# mk312.net
KiCad netlist of a schematic drawn in EAGLE
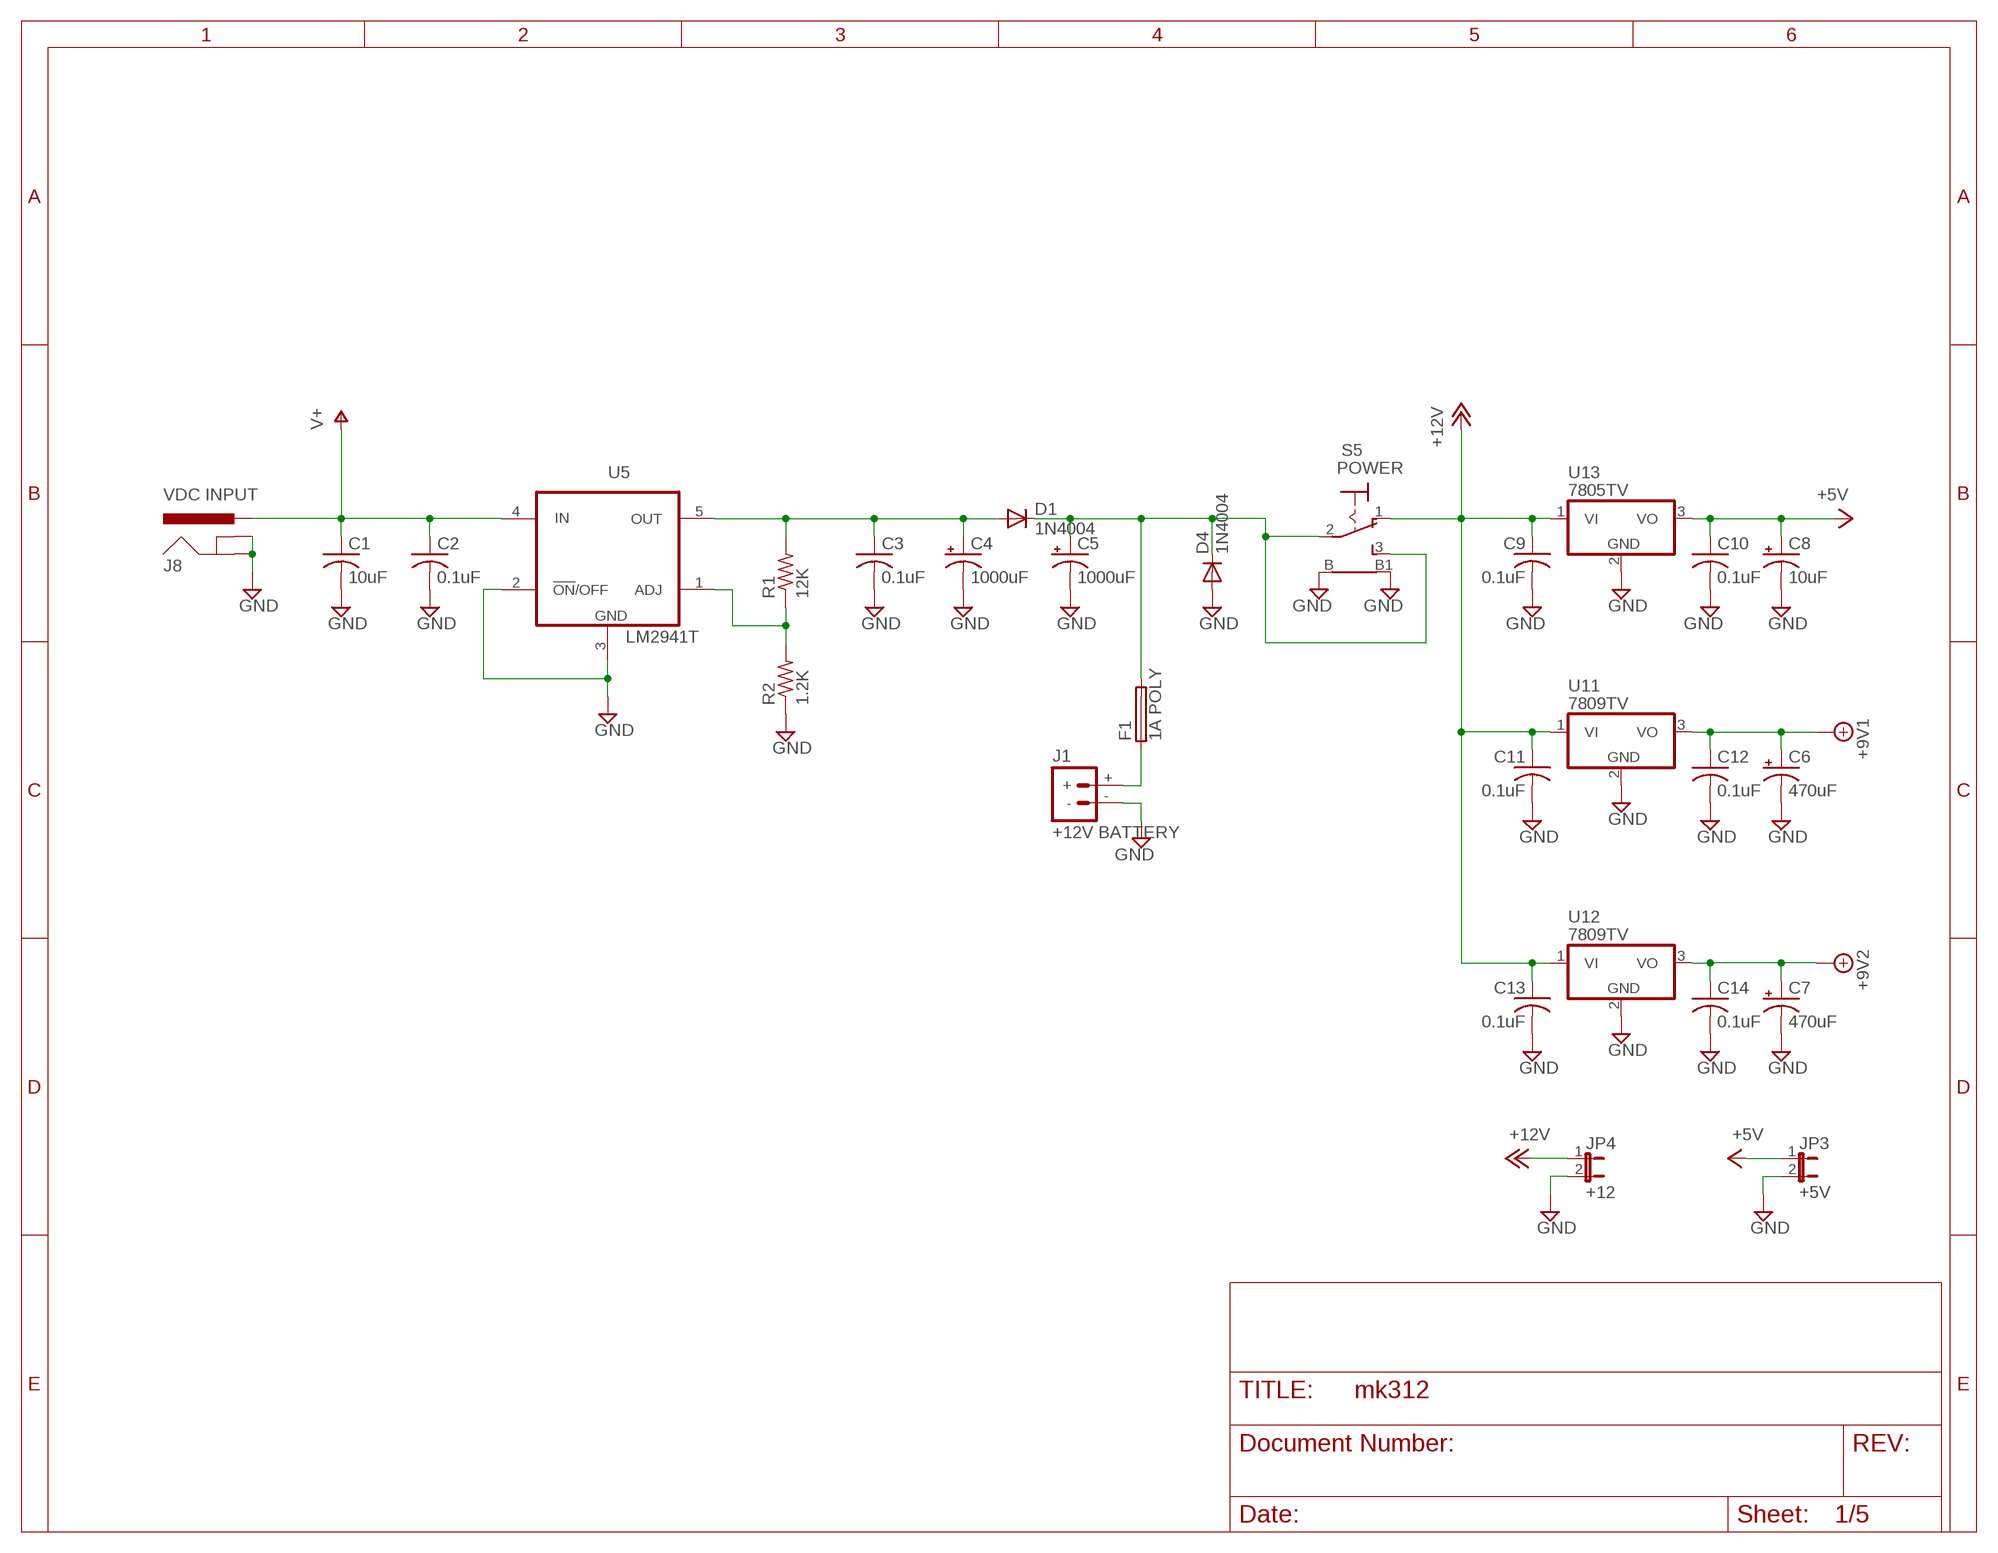
[diagram p0: schematic, sheet 1]
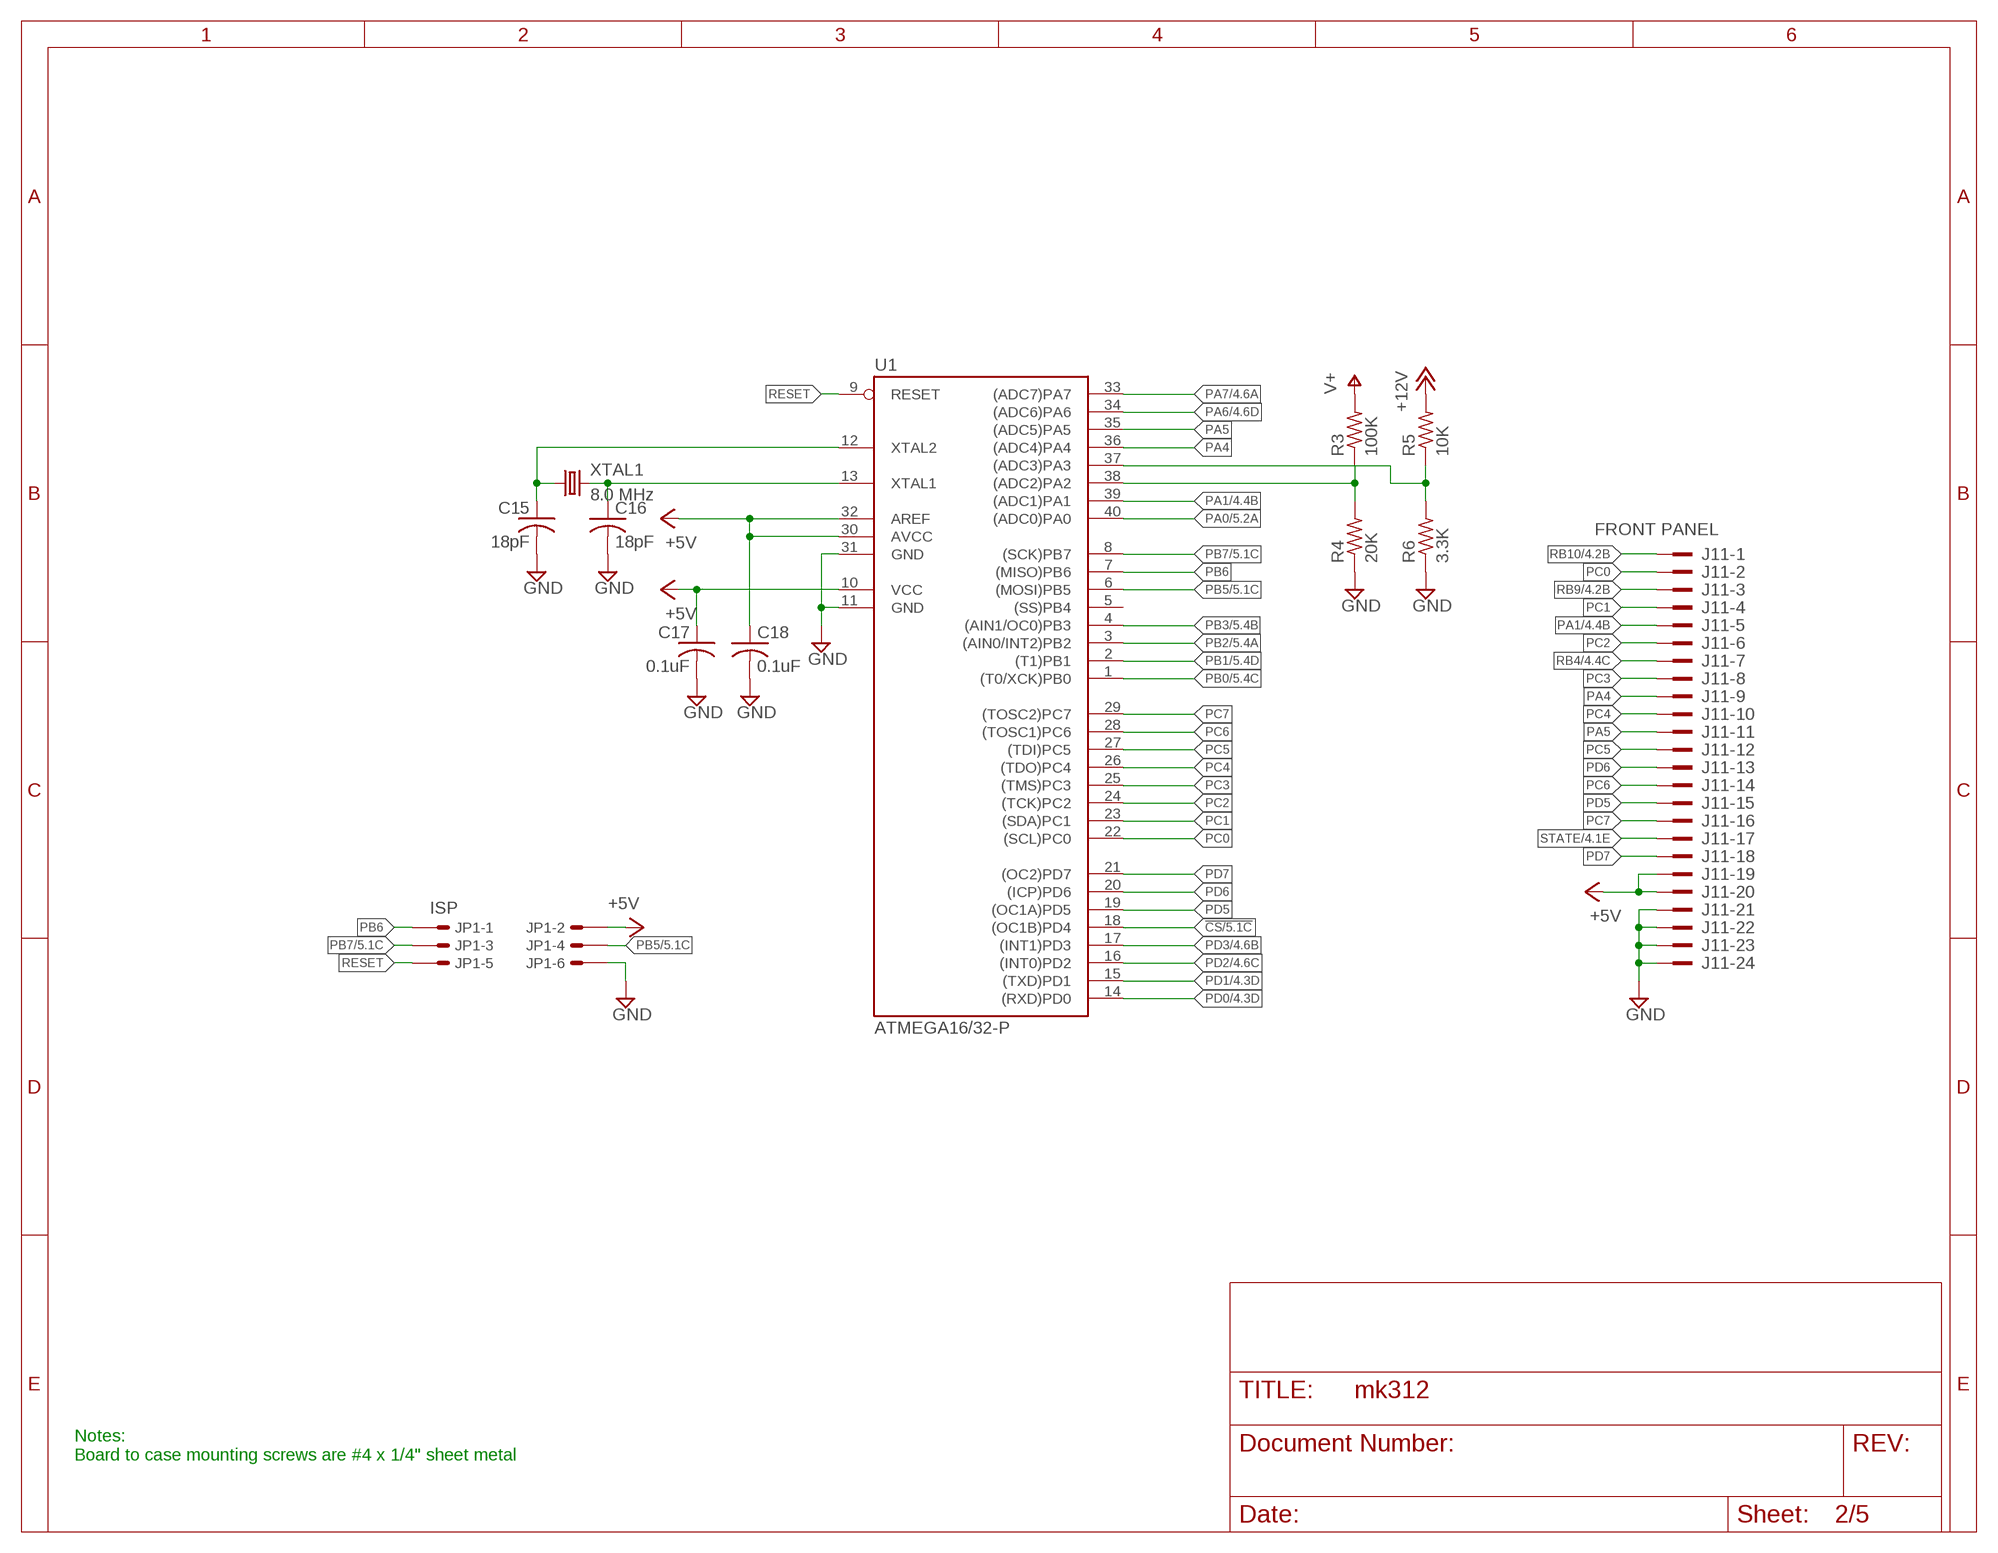
[diagram p1: schematic, sheet 2]
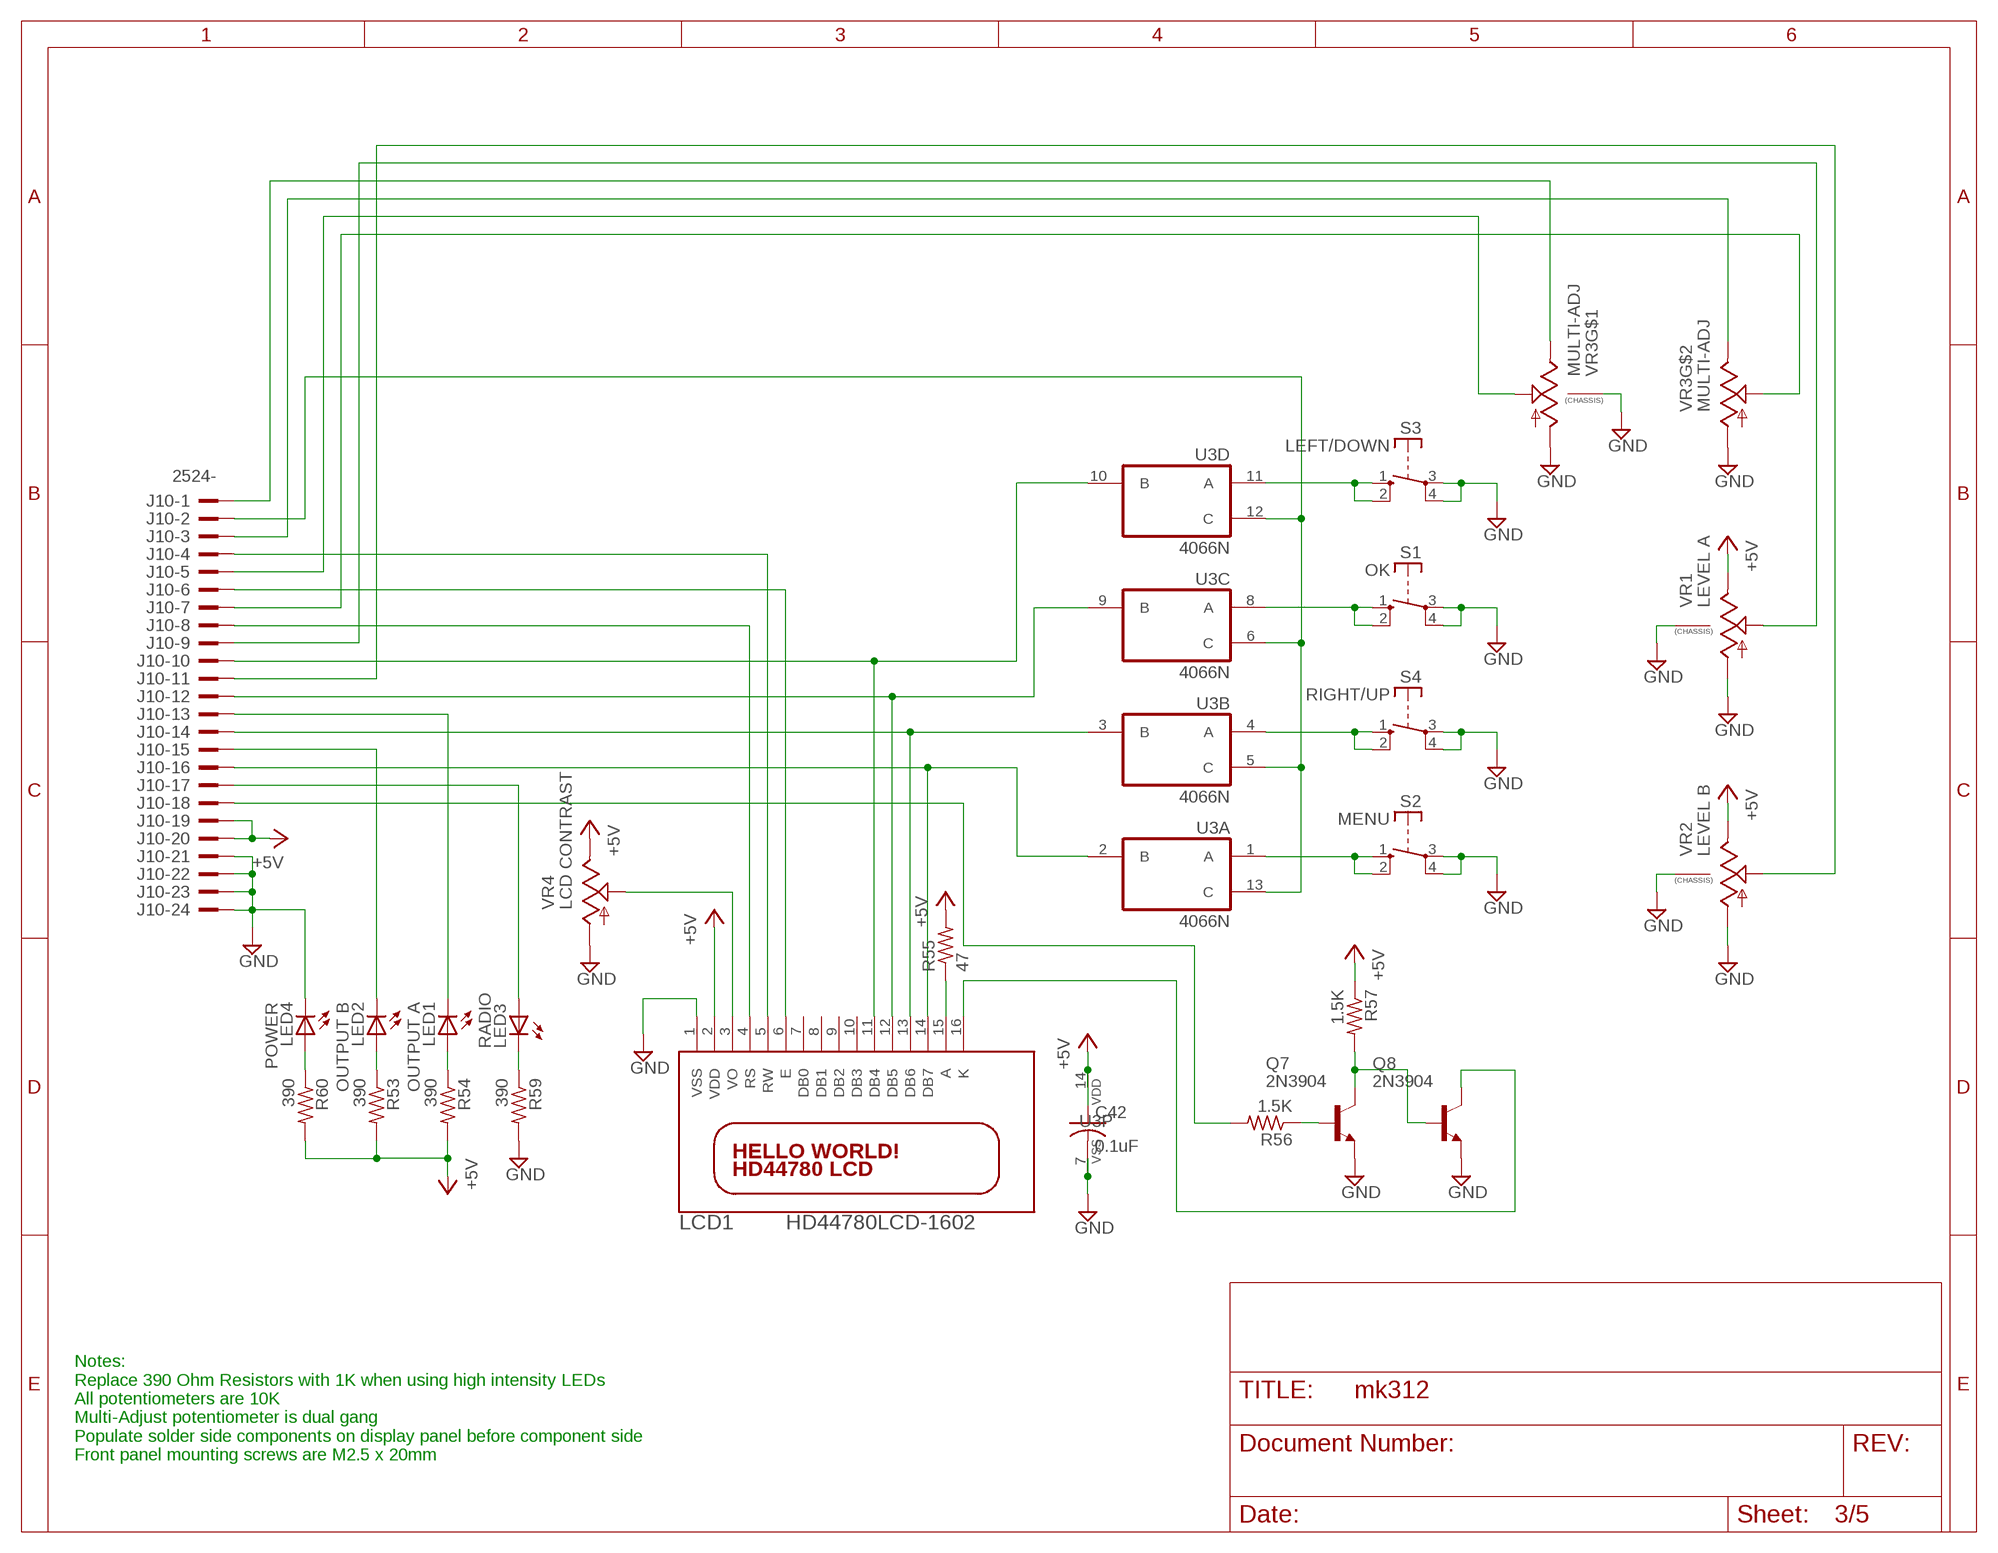
[diagram p2: schematic, sheet 3]
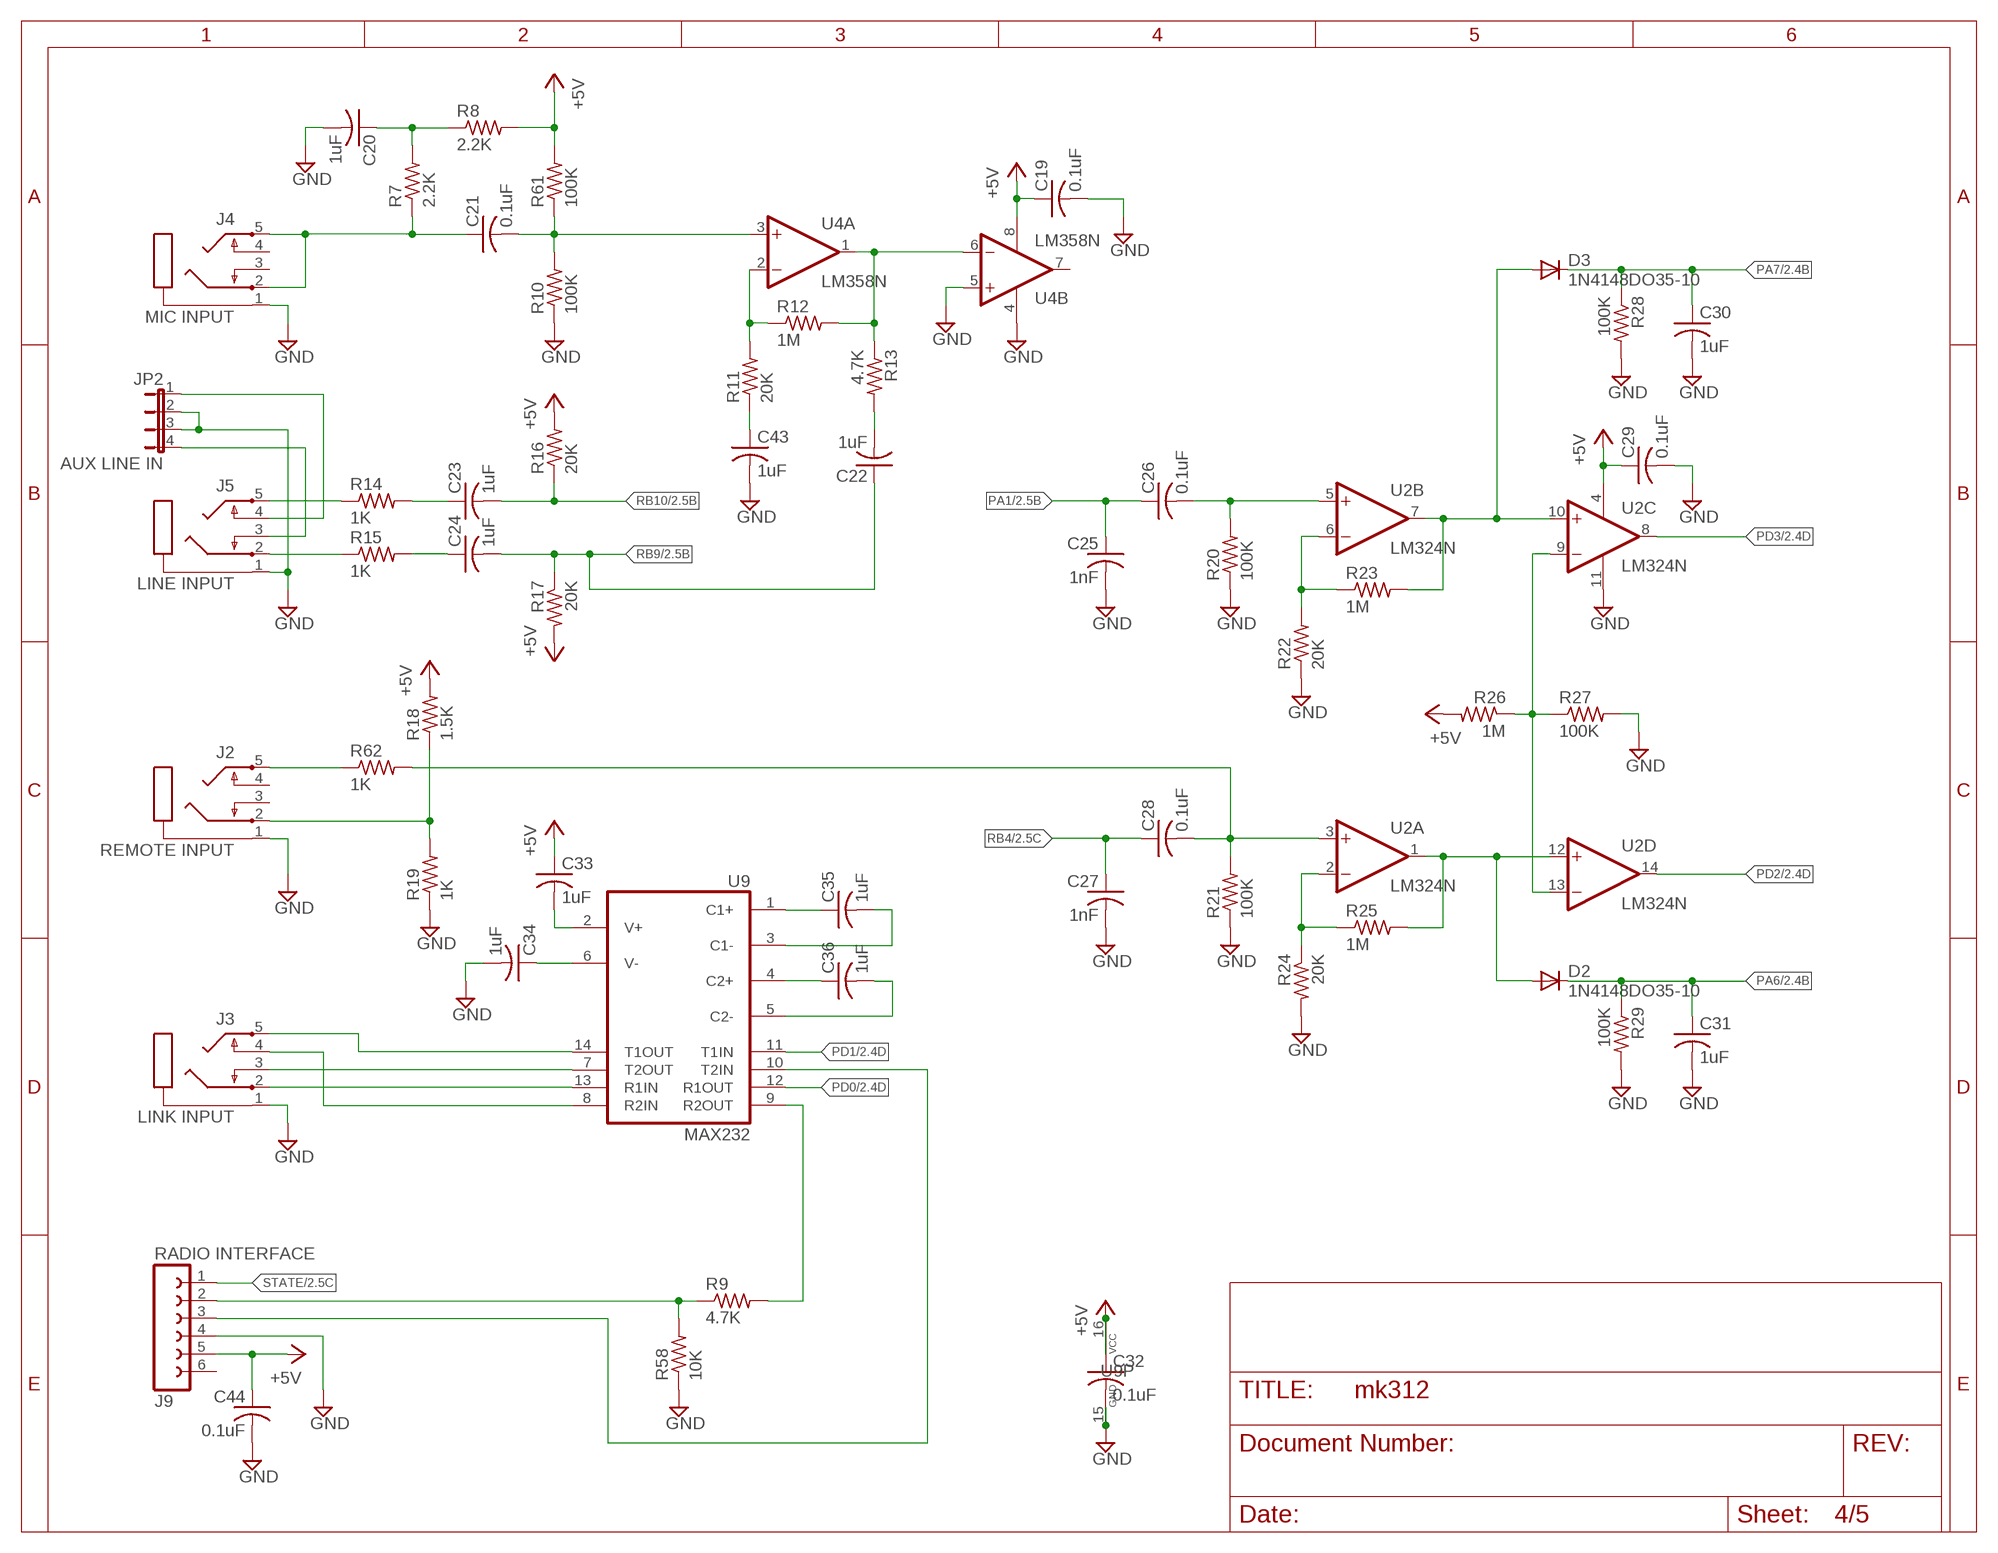
[diagram p3: schematic, sheet 4]
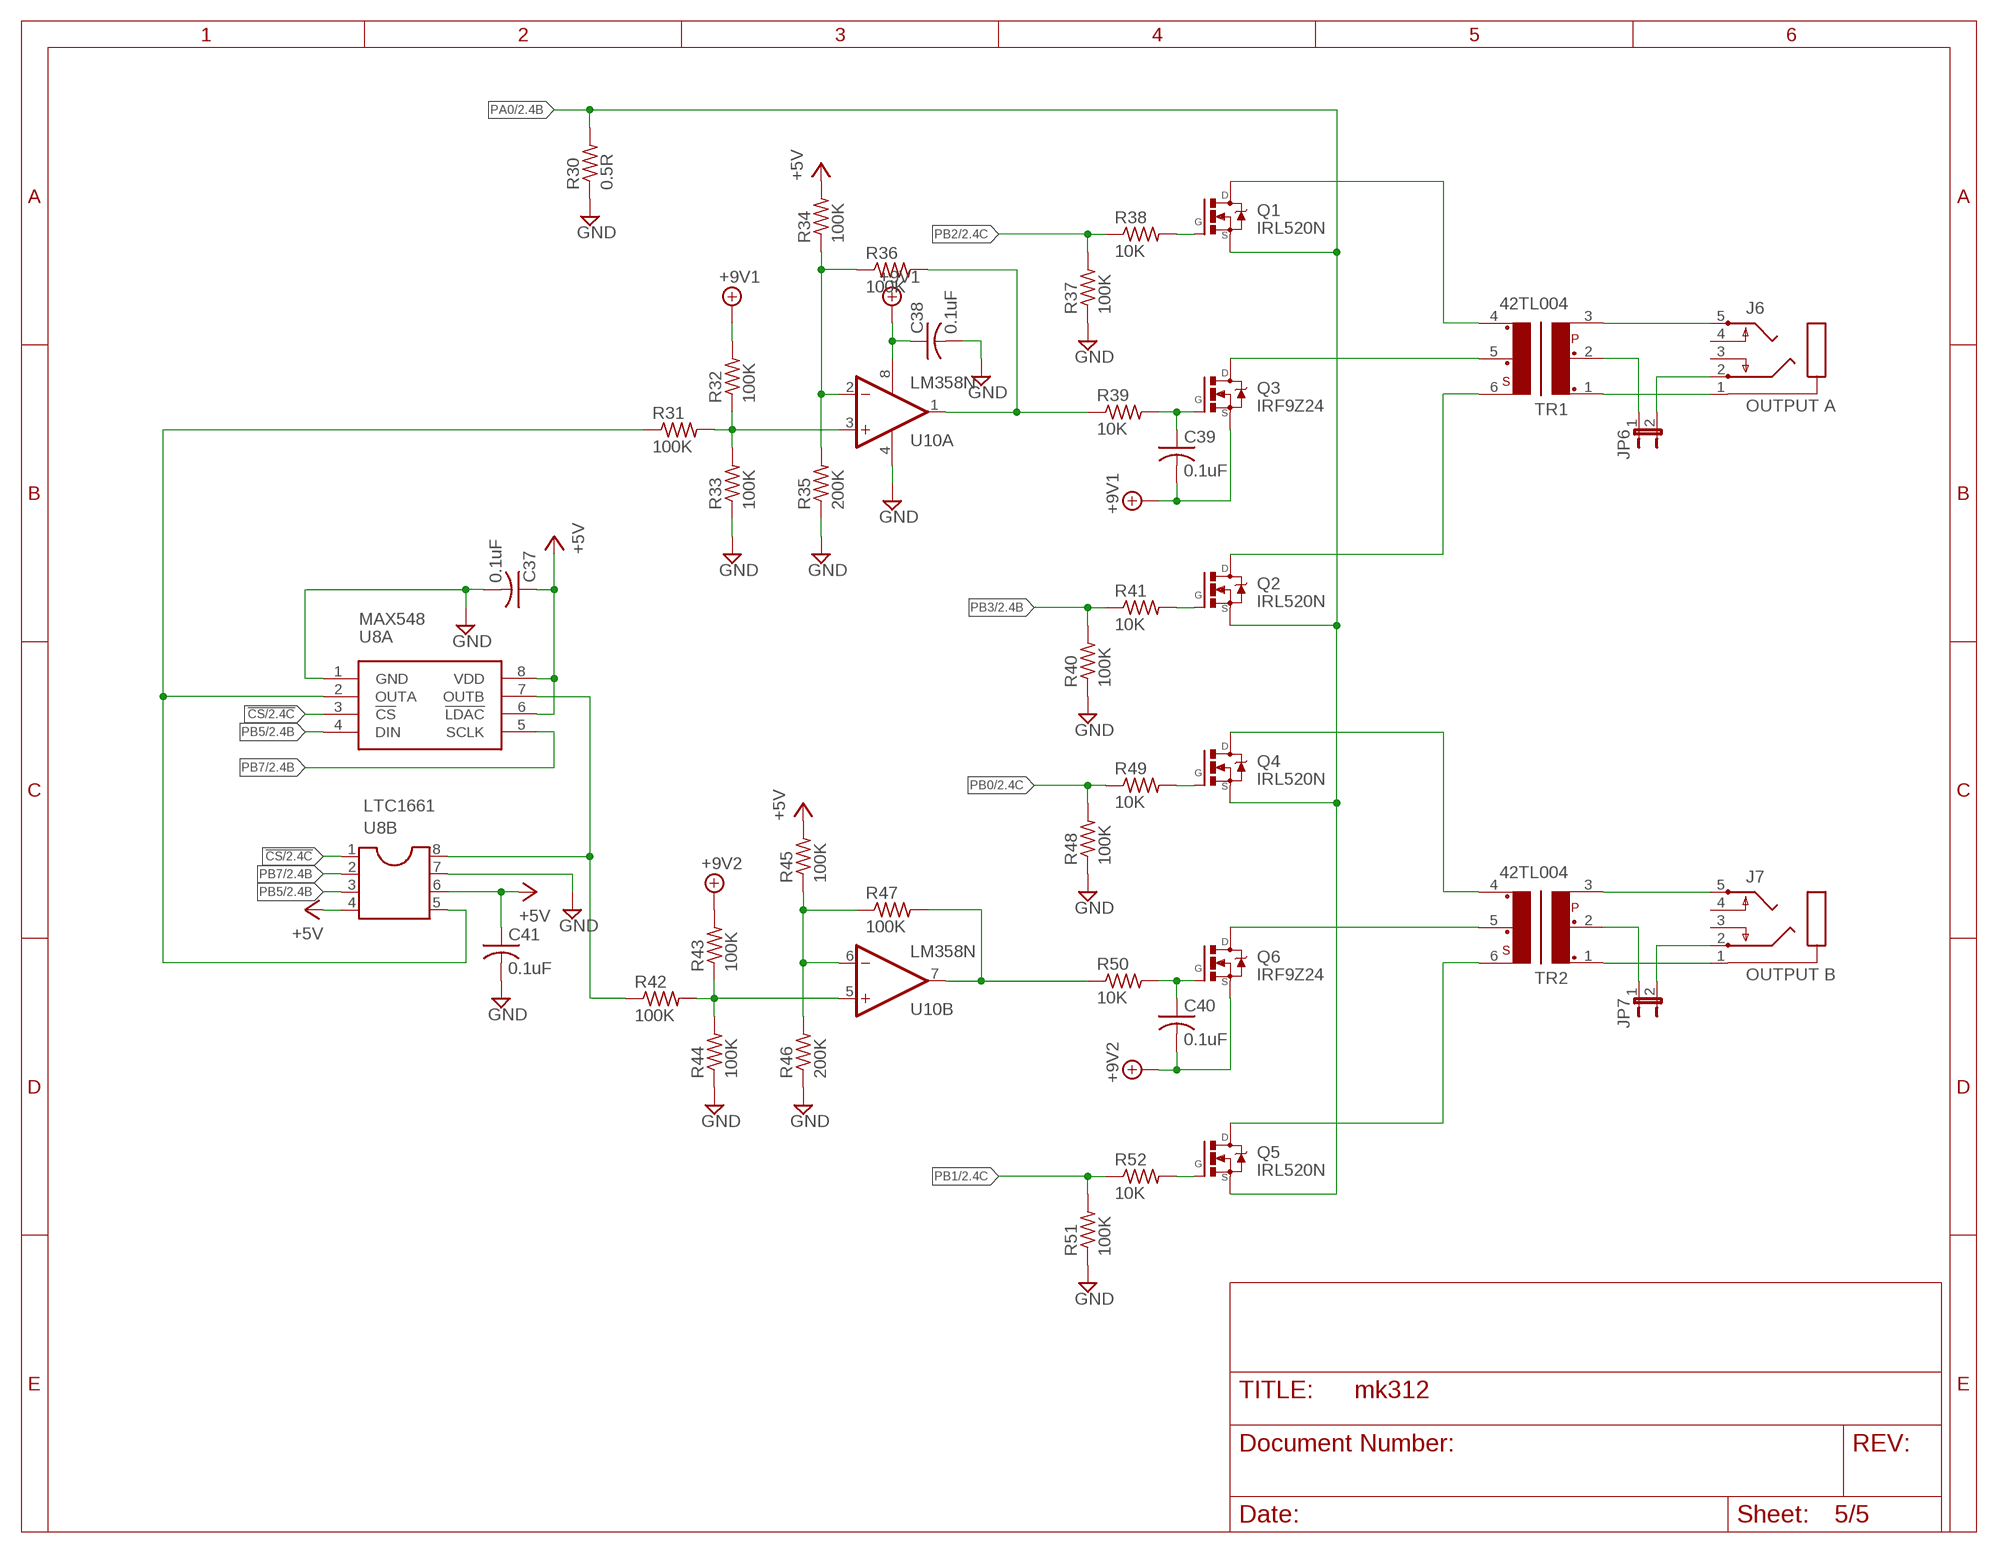
[diagram p4: schematic, sheet 5]

(export (version "E")
  (design (tool "Eeschema 10.0.6"))
  (components
    (comp (ref "C15")
      (value "18pF")
      (footprint "eagle-import:C025-024X044")
      (libsource (lib "eagle-import") (part "C-US025-024X044"))
    )
    (comp (ref "C16")
      (value "18pF")
      (footprint "eagle-import:C025-024X044")
      (libsource (lib "eagle-import") (part "C-US025-024X044"))
    )
    (comp (ref "C17")
      (value "0.1uF")
      (footprint "eagle-import:C025-024X044")
      (libsource (lib "eagle-import") (part "C-US025-024X044"))
    )
    (comp (ref "C18")
      (value "0.1uF")
      (footprint "eagle-import:C025-024X044")
      (libsource (lib "eagle-import") (part "C-US025-024X044"))
    )
    (comp (ref "J11")
      (value "FRONT PANEL")
      (footprint "eagle-import:PAK100_2500-24")
      (libsource (lib "eagle-import") (part "2524-"))
    )
    (comp (ref "JP1")
      (value "ISP")
      (footprint "eagle-import:057-006-1")
      (libsource (lib "eagle-import") (part "057-006-1"))
    )
    (comp (ref "R3")
      (value "100K")
      (footprint "eagle-import:0207_10")
      (libsource (lib "eagle-import") (part "R-US_0207/10"))
    )
    (comp (ref "R4")
      (value "20K")
      (footprint "eagle-import:0207_10")
      (libsource (lib "eagle-import") (part "R-US_0207/10"))
    )
    (comp (ref "R5")
      (value "10K")
      (footprint "eagle-import:0207_10")
      (libsource (lib "eagle-import") (part "R-US_0207/10"))
    )
    (comp (ref "R6")
      (value "3.3K")
      (footprint "eagle-import:0207_10")
      (libsource (lib "eagle-import") (part "R-US_0207/10"))
    )
    (comp (ref "U1")
      (value "ATMEGA16/32-P")
      (footprint "eagle-import:DIL40")
      (fields (field (name "MPN") "ATMEGA16-16PU"))
      (libsource (lib "eagle-import") (part "MEGA16-P"))
    )
    (comp (ref "XTAL1")
      (value "8.0 MHz")
      (footprint "eagle-import:HC49_S")
      (libsource (lib "eagle-import") (part "CRYSTALHC49S"))
    )
    (comp (ref "C1")
      (value "10uF")
      (footprint "eagle-import:C050-024X044")
      (libsource (lib "eagle-import") (part "C-US050-024X044"))
    )
    (comp (ref "C2")
      (value "0.1uF")
      (footprint "eagle-import:C025-024X044")
      (libsource (lib "eagle-import") (part "C-US025-024X044"))
    )
    (comp (ref "C3")
      (value "0.1uF")
      (footprint "eagle-import:C025-024X044")
      (libsource (lib "eagle-import") (part "C-US025-024X044"))
    )
    (comp (ref "C4")
      (value "1000uF")
      (footprint "eagle-import:E5-10,5")
      (libsource (lib "eagle-import") (part "CPOL-USE5-10.5"))
    )
    (comp (ref "C5")
      (value "1000uF")
      (footprint "eagle-import:E5-10,5")
      (libsource (lib "eagle-import") (part "CPOL-USE5-10.5"))
    )
    (comp (ref "C6")
      (value "470uF")
      (footprint "eagle-import:E3,5-8")
      (libsource (lib "eagle-import") (part "CPOL-USE3.5-8"))
    )
    (comp (ref "C7")
      (value "470uF")
      (footprint "eagle-import:E3,5-8")
      (libsource (lib "eagle-import") (part "CPOL-USE3.5-8"))
    )
    (comp (ref "C8")
      (value "10uF")
      (footprint "eagle-import:E2,5-7")
      (libsource (lib "eagle-import") (part "CPOL-USE2.5-7"))
    )
    (comp (ref "C9")
      (value "0.1uF")
      (footprint "eagle-import:C025-024X044")
      (libsource (lib "eagle-import") (part "C-US025-024X044"))
    )
    (comp (ref "C10")
      (value "0.1uF")
      (footprint "eagle-import:C025-024X044")
      (libsource (lib "eagle-import") (part "C-US025-024X044"))
    )
    (comp (ref "C11")
      (value "0.1uF")
      (footprint "eagle-import:C025-024X044")
      (libsource (lib "eagle-import") (part "C-US025-024X044"))
    )
    (comp (ref "C12")
      (value "0.1uF")
      (footprint "eagle-import:C025-024X044")
      (libsource (lib "eagle-import") (part "C-US025-024X044"))
    )
    (comp (ref "C13")
      (value "0.1uF")
      (footprint "eagle-import:C025-024X044")
      (libsource (lib "eagle-import") (part "C-US025-024X044"))
    )
    (comp (ref "C14")
      (value "0.1uF")
      (footprint "eagle-import:C025-024X044")
      (libsource (lib "eagle-import") (part "C-US025-024X044"))
    )
    (comp (ref "D1")
      (value "1N4004")
      (footprint "eagle-import:DO41-10")
      (libsource (lib "eagle-import") (part "1N4004"))
    )
    (comp (ref "D4")
      (value "1N4004")
      (footprint "eagle-import:DO41-10")
      (libsource (lib "eagle-import") (part "1N4004"))
    )
    (comp (ref "F1")
      (value "1A POLY")
      (footprint "eagle-import:LITTLEFUSE")
      (libsource (lib "eagle-import") (part "LITTLEFUSE"))
    )
    (comp (ref "J1")
      (value "+12V BATTERY")
      (footprint "eagle-import:DEANS")
      (libsource (lib "eagle-import") (part "BATTERY_CONNDEANS"))
    )
    (comp (ref "J8")
      (value "VDC INPUT")
      (footprint "eagle-import:POWER_JACK_SLOT")
      (libsource (lib "eagle-import") (part "POWER_JACKSLT"))
    )
    (comp (ref "JP3")
      (value "+5V")
      (footprint "eagle-import:JP1")
      (libsource (lib "eagle-import") (part "JP1E"))
    )
    (comp (ref "JP4")
      (value "+12")
      (footprint "eagle-import:JP1")
      (libsource (lib "eagle-import") (part "JP1E"))
    )
    (comp (ref "R1")
      (value "12K")
      (footprint "eagle-import:0207_10")
      (libsource (lib "eagle-import") (part "R-US_0207/10"))
    )
    (comp (ref "R2")
      (value "1.2K")
      (footprint "eagle-import:0207_10")
      (libsource (lib "eagle-import") (part "R-US_0207/10"))
    )
    (comp (ref "S5")
      (value "POWER")
      (footprint "eagle-import:LPV-1")
      (libsource (lib "eagle-import") (part "LPV-1"))
    )
    (comp (ref "U5")
      (value "LM2941T")
      (footprint "eagle-import:TO220-5")
      (libsource (lib "eagle-import") (part "LM2941T"))
    )
    (comp (ref "U11")
      (value "7809TV")
      (footprint "eagle-import:TO220V")
      (libsource (lib "eagle-import") (part "78TV05"))
    )
    (comp (ref "U12")
      (value "7809TV")
      (footprint "eagle-import:TO220V")
      (libsource (lib "eagle-import") (part "78TV05"))
    )
    (comp (ref "U13")
      (value "7805TV")
      (footprint "eagle-import:TO220V")
      (libsource (lib "eagle-import") (part "78TV05"))
    )
    (comp (ref "C37")
      (value "0.1uF")
      (footprint "eagle-import:C025-024X044")
      (libsource (lib "eagle-import") (part "C-US025-024X044"))
    )
    (comp (ref "C38")
      (value "0.1uF")
      (footprint "eagle-import:C025-024X044")
      (libsource (lib "eagle-import") (part "C-US025-024X044"))
    )
    (comp (ref "C39")
      (value "0.1uF")
      (footprint "eagle-import:C025-024X044")
      (libsource (lib "eagle-import") (part "C-US025-024X044"))
    )
    (comp (ref "C40")
      (value "0.1uF")
      (footprint "eagle-import:C025-024X044")
      (libsource (lib "eagle-import") (part "C-US025-024X044"))
    )
    (comp (ref "C41")
      (value "0.1uF")
      (footprint "eagle-import:C025-024X044")
      (libsource (lib "eagle-import") (part "C-US025-024X044"))
    )
    (comp (ref "J6")
      (value "OUTPUT A")
      (footprint "eagle-import:STX3100")
      (libsource (lib "eagle-import") (part "STEREOJACK"))
    )
    (comp (ref "J7")
      (value "OUTPUT B")
      (footprint "eagle-import:STX3100")
      (libsource (lib "eagle-import") (part "STEREOJACK"))
    )
    (comp (ref "JP6")
      (value "JP1E")
      (footprint "eagle-import:JP1")
      (libsource (lib "eagle-import") (part "JP1E"))
    )
    (comp (ref "JP7")
      (value "JP1E")
      (footprint "eagle-import:JP1")
      (libsource (lib "eagle-import") (part "JP1E"))
    )
    (comp (ref "Q1")
      (value "IRL520N")
      (footprint "eagle-import:TO220V")
      (libsource (lib "eagle-import") (part "IRL530N-V"))
    )
    (comp (ref "Q2")
      (value "IRL520N")
      (footprint "eagle-import:TO220V")
      (libsource (lib "eagle-import") (part "IRL530N-V"))
    )
    (comp (ref "Q3")
      (value "IRF9Z24")
      (footprint "eagle-import:TO220V")
      (libsource (lib "eagle-import") (part "IRL530N-V"))
    )
    (comp (ref "Q4")
      (value "IRL520N")
      (footprint "eagle-import:TO220V")
      (libsource (lib "eagle-import") (part "IRL530N-V"))
    )
    (comp (ref "Q5")
      (value "IRL520N")
      (footprint "eagle-import:TO220V")
      (libsource (lib "eagle-import") (part "IRL530N-V"))
    )
    (comp (ref "Q6")
      (value "IRF9Z24")
      (footprint "eagle-import:TO220V")
      (libsource (lib "eagle-import") (part "IRL530N-V"))
    )
    (comp (ref "R30")
      (value "0.5R")
      (footprint "eagle-import:0309_12")
      (libsource (lib "eagle-import") (part "R-US_0309/12"))
    )
    (comp (ref "R31")
      (value "100K")
      (footprint "eagle-import:0207_10")
      (libsource (lib "eagle-import") (part "R-US_0207/10"))
    )
    (comp (ref "R32")
      (value "100K")
      (footprint "eagle-import:0207_10")
      (libsource (lib "eagle-import") (part "R-US_0207/10"))
    )
    (comp (ref "R33")
      (value "100K")
      (footprint "eagle-import:0207_10")
      (libsource (lib "eagle-import") (part "R-US_0207/10"))
    )
    (comp (ref "R34")
      (value "100K")
      (footprint "eagle-import:0207_10")
      (libsource (lib "eagle-import") (part "R-US_0207/10"))
    )
    (comp (ref "R35")
      (value "200K")
      (footprint "eagle-import:0207_10")
      (libsource (lib "eagle-import") (part "R-US_0207/10"))
    )
    (comp (ref "R36")
      (value "100K")
      (footprint "eagle-import:0207_10")
      (libsource (lib "eagle-import") (part "R-US_0207/10"))
    )
    (comp (ref "R37")
      (value "100K")
      (footprint "eagle-import:0207_10")
      (libsource (lib "eagle-import") (part "R-US_0207/10"))
    )
    (comp (ref "R38")
      (value "10K")
      (footprint "eagle-import:0207_10")
      (libsource (lib "eagle-import") (part "R-US_0207/10"))
    )
    (comp (ref "R39")
      (value "10K")
      (footprint "eagle-import:0207_10")
      (libsource (lib "eagle-import") (part "R-US_0207/10"))
    )
    (comp (ref "R40")
      (value "100K")
      (footprint "eagle-import:0207_10")
      (libsource (lib "eagle-import") (part "R-US_0207/10"))
    )
    (comp (ref "R41")
      (value "10K")
      (footprint "eagle-import:0207_10")
      (libsource (lib "eagle-import") (part "R-US_0207/10"))
    )
    (comp (ref "R42")
      (value "100K")
      (footprint "eagle-import:0207_10")
      (libsource (lib "eagle-import") (part "R-US_0207/10"))
    )
    (comp (ref "R43")
      (value "100K")
      (footprint "eagle-import:0207_10")
      (libsource (lib "eagle-import") (part "R-US_0207/10"))
    )
    (comp (ref "R44")
      (value "100K")
      (footprint "eagle-import:0207_10")
      (libsource (lib "eagle-import") (part "R-US_0207/10"))
    )
    (comp (ref "R45")
      (value "100K")
      (footprint "eagle-import:0207_10")
      (libsource (lib "eagle-import") (part "R-US_0207/10"))
    )
    (comp (ref "R46")
      (value "200K")
      (footprint "eagle-import:0207_10")
      (libsource (lib "eagle-import") (part "R-US_0207/10"))
    )
    (comp (ref "R47")
      (value "100K")
      (footprint "eagle-import:0207_10")
      (libsource (lib "eagle-import") (part "R-US_0207/10"))
    )
    (comp (ref "R48")
      (value "100K")
      (footprint "eagle-import:0207_10")
      (libsource (lib "eagle-import") (part "R-US_0207/10"))
    )
    (comp (ref "R49")
      (value "10K")
      (footprint "eagle-import:0207_10")
      (libsource (lib "eagle-import") (part "R-US_0207/10"))
    )
    (comp (ref "R50")
      (value "10K")
      (footprint "eagle-import:0207_10")
      (libsource (lib "eagle-import") (part "R-US_0207/10"))
    )
    (comp (ref "R51")
      (value "100K")
      (footprint "eagle-import:0207_10")
      (libsource (lib "eagle-import") (part "R-US_0207/10"))
    )
    (comp (ref "R52")
      (value "10K")
      (footprint "eagle-import:0207_10")
      (libsource (lib "eagle-import") (part "R-US_0207/10"))
    )
    (comp (ref "TR1")
      (value "42TL004")
      (footprint "eagle-import:42TL")
      (libsource (lib "eagle-import") (part "42T?L023"))
    )
    (comp (ref "TR2")
      (value "42TL004")
      (footprint "eagle-import:42TL")
      (libsource (lib "eagle-import") (part "42T?L023"))
    )
    (comp (ref "U8A")
      (value "MAX548")
      (footprint "eagle-import:DIL08")
      (libsource (lib "eagle-import") (part "MAX548"))
    )
    (comp (ref "U8B")
      (value "LTC1661")
      (footprint "eagle-import:SOCKET-08")
      (libsource (lib "eagle-import") (part "DIL8S"))
    )
    (comp (ref "U10")
      (value "LM358N")
      (footprint "eagle-import:DIL08")
      (libsource (lib "eagle-import") (part "LM358N"))
    )
    (comp (ref "C42")
      (value "0.1uF")
      (footprint "eagle-import:C025-024X044")
      (libsource (lib "eagle-import") (part "C-US025-024X044"))
    )
    (comp (ref "J10")
      (value "2524-")
      (footprint "eagle-import:PAK100_2500-24")
      (libsource (lib "eagle-import") (part "2524-"))
    )
    (comp (ref "LCD1")
      (value "HD44780LCD-1602")
      (footprint "eagle-import:LCD1602")
      (libsource (lib "eagle-import") (part "HD44780LCD-1602"))
    )
    (comp (ref "LED1")
      (value "OUTPUT A")
      (footprint "eagle-import:LED5MM")
      (libsource (lib "eagle-import") (part "LED5MM"))
    )
    (comp (ref "LED2")
      (value "OUTPUT B")
      (footprint "eagle-import:LED5MM")
      (libsource (lib "eagle-import") (part "LED5MM"))
    )
    (comp (ref "LED3")
      (value "RADIO")
      (footprint "eagle-import:LED5MM")
      (libsource (lib "eagle-import") (part "LED5MM"))
    )
    (comp (ref "LED4")
      (value "POWER")
      (footprint "eagle-import:LED5MM")
      (libsource (lib "eagle-import") (part "LED5MM"))
    )
    (comp (ref "Q7")
      (value "2N3904")
      (footprint "eagle-import:TO92")
      (libsource (lib "eagle-import") (part "2N3904"))
    )
    (comp (ref "Q8")
      (value "2N3904")
      (footprint "eagle-import:TO92")
      (libsource (lib "eagle-import") (part "2N3904"))
    )
    (comp (ref "R53")
      (value "390")
      (footprint "eagle-import:0207_10")
      (libsource (lib "eagle-import") (part "R-US_0207/10"))
    )
    (comp (ref "R54")
      (value "390")
      (footprint "eagle-import:0207_10")
      (libsource (lib "eagle-import") (part "R-US_0207/10"))
    )
    (comp (ref "R55")
      (value "47")
      (footprint "eagle-import:0207_10")
      (libsource (lib "eagle-import") (part "R-US_0207/10"))
    )
    (comp (ref "R56")
      (value "1.5K")
      (footprint "eagle-import:0207_10")
      (libsource (lib "eagle-import") (part "R-US_0207/10"))
    )
    (comp (ref "R57")
      (value "1.5K")
      (footprint "eagle-import:0207_10")
      (libsource (lib "eagle-import") (part "R-US_0207/10"))
    )
    (comp (ref "R59")
      (value "390")
      (footprint "eagle-import:0207_10")
      (libsource (lib "eagle-import") (part "R-US_0207/10"))
    )
    (comp (ref "R60")
      (value "390")
      (footprint "eagle-import:0207_10")
      (libsource (lib "eagle-import") (part "R-US_0207/10"))
    )
    (comp (ref "S1")
      (value "OK")
      (footprint "eagle-import:DTE6K")
      (libsource (lib "eagle-import") (part "DTE6K"))
    )
    (comp (ref "S2")
      (value "MENU")
      (footprint "eagle-import:DTE6K")
      (libsource (lib "eagle-import") (part "DTE6K"))
    )
    (comp (ref "S3")
      (value "LEFT/DOWN")
      (footprint "eagle-import:DTE6K")
      (libsource (lib "eagle-import") (part "DTE6K"))
    )
    (comp (ref "S4")
      (value "RIGHT/UP")
      (footprint "eagle-import:DTE6K")
      (libsource (lib "eagle-import") (part "DTE6K"))
    )
    (comp (ref "U3")
      (value "4066N")
      (footprint "eagle-import:DIL14")
      (libsource (lib "eagle-import") (part "4066N"))
    )
    (comp (ref "VR1")
      (value "LEVEL A")
      (footprint "eagle-import:9MM_SNAP-IN_POT")
      (libsource (lib "eagle-import") (part "9MM_SNAP-IN_POT_CHASSIS"))
    )
    (comp (ref "VR2")
      (value "LEVEL B")
      (footprint "eagle-import:9MM_SNAP-IN_POT")
      (libsource (lib "eagle-import") (part "9MM_SNAP-IN_POT_CHASSIS"))
    )
    (comp (ref "VR3")
      (value "MULTI-ADJ")
      (footprint "eagle-import:DUAL_9MM_SNAP-IN_POT")
      (libsource (lib "eagle-import") (part "ALPHA-9MM-DUALPOT"))
    )
    (comp (ref "VR4")
      (value "LCD CONTRAST")
      (footprint "eagle-import:B25P")
      (libsource (lib "eagle-import") (part "TRIM_US-B25P"))
    )
    (comp (ref "C19")
      (value "0.1uF")
      (footprint "eagle-import:C025-024X044")
      (libsource (lib "eagle-import") (part "C-US025-024X044"))
    )
    (comp (ref "C20")
      (value "1uF")
      (footprint "eagle-import:C025-024X044")
      (libsource (lib "eagle-import") (part "C-US025-024X044"))
    )
    (comp (ref "C21")
      (value "0.1uF")
      (footprint "eagle-import:C025-024X044")
      (libsource (lib "eagle-import") (part "C-US025-024X044"))
    )
    (comp (ref "C22")
      (value "1uF")
      (footprint "eagle-import:C025-024X044")
      (libsource (lib "eagle-import") (part "C-US025-024X044"))
    )
    (comp (ref "C23")
      (value "1uF")
      (footprint "eagle-import:C025-024X044")
      (libsource (lib "eagle-import") (part "C-US025-024X044"))
    )
    (comp (ref "C24")
      (value "1uF")
      (footprint "eagle-import:C025-024X044")
      (libsource (lib "eagle-import") (part "C-US025-024X044"))
    )
    (comp (ref "C25")
      (value "1nF")
      (footprint "eagle-import:C025-024X044")
      (libsource (lib "eagle-import") (part "C-US025-024X044"))
    )
    (comp (ref "C26")
      (value "0.1uF")
      (footprint "eagle-import:C025-024X044")
      (libsource (lib "eagle-import") (part "C-US025-024X044"))
    )
    (comp (ref "C27")
      (value "1nF")
      (footprint "eagle-import:C025-024X044")
      (libsource (lib "eagle-import") (part "C-US025-024X044"))
    )
    (comp (ref "C28")
      (value "0.1uF")
      (footprint "eagle-import:C025-024X044")
      (libsource (lib "eagle-import") (part "C-US025-024X044"))
    )
    (comp (ref "C29")
      (value "0.1uF")
      (footprint "eagle-import:C025-024X044")
      (libsource (lib "eagle-import") (part "C-US025-024X044"))
    )
    (comp (ref "C30")
      (value "1uF")
      (footprint "eagle-import:C025-024X044")
      (libsource (lib "eagle-import") (part "C-US025-024X044"))
    )
    (comp (ref "C31")
      (value "1uF")
      (footprint "eagle-import:C025-024X044")
      (libsource (lib "eagle-import") (part "C-US025-024X044"))
    )
    (comp (ref "C32")
      (value "0.1uF")
      (footprint "eagle-import:C025-024X044")
      (libsource (lib "eagle-import") (part "C-US025-024X044"))
    )
    (comp (ref "C33")
      (value "1uF")
      (footprint "eagle-import:C025-024X044")
      (libsource (lib "eagle-import") (part "C-US025-024X044"))
    )
    (comp (ref "C34")
      (value "1uF")
      (footprint "eagle-import:C025-024X044")
      (libsource (lib "eagle-import") (part "C-US025-024X044"))
    )
    (comp (ref "C35")
      (value "1uF")
      (footprint "eagle-import:C025-024X044")
      (libsource (lib "eagle-import") (part "C-US025-024X044"))
    )
    (comp (ref "C36")
      (value "1uF")
      (footprint "eagle-import:C025-024X044")
      (libsource (lib "eagle-import") (part "C-US025-024X044"))
    )
    (comp (ref "C43")
      (value "1uF")
      (footprint "eagle-import:C025-024X044")
      (libsource (lib "eagle-import") (part "C-US025-024X044"))
    )
    (comp (ref "C44")
      (value "0.1uF")
      (footprint "eagle-import:C025-024X044")
      (libsource (lib "eagle-import") (part "C-US025-024X044"))
    )
    (comp (ref "D2")
      (value "1N4148DO35-10")
      (footprint "eagle-import:DO35-10")
      (libsource (lib "eagle-import") (part "1N4148DO35-10"))
    )
    (comp (ref "D3")
      (value "1N4148DO35-10")
      (footprint "eagle-import:DO35-10")
      (libsource (lib "eagle-import") (part "1N4148DO35-10"))
    )
    (comp (ref "J2")
      (value "REMOTE INPUT")
      (footprint "eagle-import:STX3100")
      (libsource (lib "eagle-import") (part "STEREOJACK"))
    )
    (comp (ref "J3")
      (value "LINK INPUT")
      (footprint "eagle-import:STX3100")
      (libsource (lib "eagle-import") (part "STEREOJACK"))
    )
    (comp (ref "J4")
      (value "MIC INPUT")
      (footprint "eagle-import:STX3100")
      (libsource (lib "eagle-import") (part "STEREOJACK"))
    )
    (comp (ref "J5")
      (value "LINE INPUT")
      (footprint "eagle-import:STX3100")
      (libsource (lib "eagle-import") (part "STEREOJACK"))
    )
    (comp (ref "J9")
      (value "RADIO INTERFACE")
      (footprint "eagle-import:FE06")
      (libsource (lib "eagle-import") (part "FE06-1"))
    )
    (comp (ref "JP2")
      (value "AUX LINE IN")
      (footprint "eagle-import:JP4")
      (libsource (lib "eagle-import") (part "JP4E"))
    )
    (comp (ref "R7")
      (value "2.2K")
      (footprint "eagle-import:0207_10")
      (libsource (lib "eagle-import") (part "R-US_0207/10"))
    )
    (comp (ref "R8")
      (value "2.2K")
      (footprint "eagle-import:0207_10")
      (libsource (lib "eagle-import") (part "R-US_0207/10"))
    )
    (comp (ref "R9")
      (value "4.7K")
      (footprint "eagle-import:0207_10")
      (libsource (lib "eagle-import") (part "R-US_0207/10"))
    )
    (comp (ref "R10")
      (value "100K")
      (footprint "eagle-import:0207_10")
      (libsource (lib "eagle-import") (part "R-US_0207/10"))
    )
    (comp (ref "R11")
      (value "20K")
      (footprint "eagle-import:0207_10")
      (libsource (lib "eagle-import") (part "R-US_0207/10"))
    )
    (comp (ref "R12")
      (value "1M")
      (footprint "eagle-import:0207_10")
      (libsource (lib "eagle-import") (part "R-US_0207/10"))
    )
    (comp (ref "R13")
      (value "4.7K")
      (footprint "eagle-import:0207_10")
      (libsource (lib "eagle-import") (part "R-US_0207/10"))
    )
    (comp (ref "R14")
      (value "1K")
      (footprint "eagle-import:0207_10")
      (libsource (lib "eagle-import") (part "R-US_0207/10"))
    )
    (comp (ref "R15")
      (value "1K")
      (footprint "eagle-import:0207_10")
      (libsource (lib "eagle-import") (part "R-US_0207/10"))
    )
    (comp (ref "R16")
      (value "20K")
      (footprint "eagle-import:0207_10")
      (libsource (lib "eagle-import") (part "R-US_0207/10"))
    )
    (comp (ref "R17")
      (value "20K")
      (footprint "eagle-import:0207_10")
      (libsource (lib "eagle-import") (part "R-US_0207/10"))
    )
    (comp (ref "R18")
      (value "1.5K")
      (footprint "eagle-import:0207_10")
      (libsource (lib "eagle-import") (part "R-US_0207/10"))
    )
    (comp (ref "R19")
      (value "1K")
      (footprint "eagle-import:0207_10")
      (libsource (lib "eagle-import") (part "R-US_0207/10"))
    )
    (comp (ref "R20")
      (value "100K")
      (footprint "eagle-import:0207_10")
      (libsource (lib "eagle-import") (part "R-US_0207/10"))
    )
    (comp (ref "R21")
      (value "100K")
      (footprint "eagle-import:0207_10")
      (libsource (lib "eagle-import") (part "R-US_0207/10"))
    )
    (comp (ref "R22")
      (value "20K")
      (footprint "eagle-import:0207_10")
      (libsource (lib "eagle-import") (part "R-US_0207/10"))
    )
    (comp (ref "R23")
      (value "1M")
      (footprint "eagle-import:0207_10")
      (libsource (lib "eagle-import") (part "R-US_0207/10"))
    )
    (comp (ref "R24")
      (value "20K")
      (footprint "eagle-import:0207_10")
      (libsource (lib "eagle-import") (part "R-US_0207/10"))
    )
    (comp (ref "R25")
      (value "1M")
      (footprint "eagle-import:0207_10")
      (libsource (lib "eagle-import") (part "R-US_0207/10"))
    )
    (comp (ref "R26")
      (value "1M")
      (footprint "eagle-import:0207_10")
      (libsource (lib "eagle-import") (part "R-US_0207/10"))
    )
    (comp (ref "R27")
      (value "100K")
      (footprint "eagle-import:0207_10")
      (libsource (lib "eagle-import") (part "R-US_0207/10"))
    )
    (comp (ref "R28")
      (value "100K")
      (footprint "eagle-import:0207_10")
      (libsource (lib "eagle-import") (part "R-US_0207/10"))
    )
    (comp (ref "R29")
      (value "100K")
      (footprint "eagle-import:0207_10")
      (libsource (lib "eagle-import") (part "R-US_0207/10"))
    )
    (comp (ref "R58")
      (value "10K")
      (footprint "eagle-import:0207_10")
      (libsource (lib "eagle-import") (part "R-US_0207/10"))
    )
    (comp (ref "R61")
      (value "100K")
      (footprint "eagle-import:0207_10")
      (libsource (lib "eagle-import") (part "R-US_0207/10"))
    )
    (comp (ref "R62")
      (value "1K")
      (footprint "eagle-import:0207_10")
      (libsource (lib "eagle-import") (part "R-US_0207/10"))
    )
    (comp (ref "U2")
      (value "LM324N")
      (footprint "eagle-import:DIL14")
      (libsource (lib "eagle-import") (part "LM324N"))
    )
    (comp (ref "U4")
      (value "LM358N")
      (footprint "eagle-import:DIL08")
      (libsource (lib "eagle-import") (part "LM358N"))
    )
    (comp (ref "U9")
      (value "MAX232")
      (footprint "eagle-import:DIL16")
      (fields (field (name "MF") "MAXIM") (field (name "MPN") "MAX232ACPE+"))
      (libsource (lib "eagle-import") (part "MAX232"))
    )
  )
  (nets
    (net (code "1") (name "+5V") (class "Default")
      (node (ref "C10") (pin "1") (pinfunction "1_1") (pintype "passive"))
      (node (ref "C17") (pin "1") (pinfunction "1_1") (pintype "passive"))
      (node (ref "C18") (pin "1") (pinfunction "1_1") (pintype "passive"))
      (node (ref "C19") (pin "1") (pinfunction "1_1") (pintype "passive"))
      (node (ref "C29") (pin "1") (pinfunction "1_1") (pintype "passive"))
      (node (ref "C32") (pin "1") (pinfunction "1_1") (pintype "passive"))
      (node (ref "C33") (pin "1") (pinfunction "1_1") (pintype "passive"))
      (node (ref "C37") (pin "1") (pinfunction "1_1") (pintype "passive"))
      (node (ref "C41") (pin "1") (pinfunction "1_1") (pintype "passive"))
      (node (ref "C42") (pin "1") (pinfunction "1_1") (pintype "passive"))
      (node (ref "C44") (pin "1") (pinfunction "1_1") (pintype "passive"))
      (node (ref "C8") (pin "+") (pinfunction "+_+") (pintype "passive"))
      (node (ref "J10") (pin "19") (pinfunction "KL_19") (pintype "passive"))
      (node (ref "J10") (pin "20") (pinfunction "KL_20") (pintype "passive"))
      (node (ref "J11") (pin "19") (pinfunction "KL_19") (pintype "passive"))
      (node (ref "J11") (pin "20") (pinfunction "KL_20") (pintype "passive"))
      (node (ref "J9") (pin "5") (pinfunction "5_5") (pintype "passive"))
      (node (ref "JP1") (pin "2") (pinfunction "S_2") (pintype "passive"))
      (node (ref "JP3") (pin "1") (pinfunction "1_1") (pintype "passive"))
      (node (ref "LCD1") (pin "2") (pinfunction "VDD_2") (pintype "power_in"))
      (node (ref "R16") (pin "2") (pinfunction "2_2") (pintype "passive"))
      (node (ref "R17") (pin "2") (pinfunction "2_2") (pintype "passive"))
      (node (ref "R18") (pin "2") (pinfunction "2_2") (pintype "passive"))
      (node (ref "R26") (pin "2") (pinfunction "2_2") (pintype "passive"))
      (node (ref "R34") (pin "2") (pinfunction "2_2") (pintype "passive"))
      (node (ref "R45") (pin "2") (pinfunction "2_2") (pintype "passive"))
      (node (ref "R53") (pin "2") (pinfunction "2_2") (pintype "passive"))
      (node (ref "R54") (pin "2") (pinfunction "2_2") (pintype "passive"))
      (node (ref "R55") (pin "2") (pinfunction "2_2") (pintype "passive"))
      (node (ref "R57") (pin "1") (pinfunction "1_1") (pintype "passive"))
      (node (ref "R60") (pin "2") (pinfunction "2_2") (pintype "passive"))
      (node (ref "R61") (pin "2") (pinfunction "2_2") (pintype "passive"))
      (node (ref "R8") (pin "2") (pinfunction "2_2") (pintype "passive"))
      (node (ref "U1") (pin "10") (pinfunction "VCC_10") (pintype "power_in"))
      (node (ref "U1") (pin "30") (pinfunction "AVCC_30") (pintype "power_in"))
      (node (ref "U1") (pin "32") (pinfunction "AREF_32") (pintype "passive"))
      (node (ref "U13") (pin "3") (pinfunction "VO_3") (pintype "passive"))
      (node (ref "U2") (pin "4") (pinfunction "V+_4") (pintype "power_in"))
      (node (ref "U3") (pin "14") (pinfunction "VDD_14") (pintype "power_in"))
      (node (ref "U4") (pin "8") (pinfunction "V+_8") (pintype "power_in"))
      (node (ref "U8A") (pin "6") (pinfunction "~{LDAC}_6") (pintype "bidirectional"))
      (node (ref "U8A") (pin "8") (pinfunction "VDD_8") (pintype "bidirectional"))
      (node (ref "U8B") (pin "4") (pinfunction "4_4") (pintype "passive"))
      (node (ref "U8B") (pin "6") (pinfunction "6_6") (pintype "passive"))
      (node (ref "U9") (pin "16") (pinfunction "VCC_16") (pintype "power_in"))
      (node (ref "VR1") (pin "3") (pinfunction "E_3") (pintype "passive"))
      (node (ref "VR2") (pin "3") (pinfunction "E_3") (pintype "passive"))
      (node (ref "VR4") (pin "E") (pinfunction "E_E") (pintype "passive"))
    )
    (net (code "2") (name "+8V") (class "Default")
      (node (ref "C12") (pin "1") (pinfunction "1_1") (pintype "passive"))
      (node (ref "C38") (pin "1") (pinfunction "1_1") (pintype "passive"))
      (node (ref "C39") (pin "2") (pinfunction "2_2") (pintype "passive"))
      (node (ref "C6") (pin "+") (pinfunction "+_+") (pintype "passive"))
      (node (ref "Q3") (pin "3") (pinfunction "S_3") (pintype "passive"))
      (node (ref "R32") (pin "2") (pinfunction "2_2") (pintype "passive"))
      (node (ref "U10") (pin "8") (pinfunction "V+_8") (pintype "power_in"))
      (node (ref "U11") (pin "3") (pinfunction "VO_3") (pintype "passive"))
    )
    (net (code "3") (name "+9V") (class "Default")
      (node (ref "C14") (pin "1") (pinfunction "1_1") (pintype "passive"))
      (node (ref "C40") (pin "2") (pinfunction "2_2") (pintype "passive"))
      (node (ref "C7") (pin "+") (pinfunction "+_+") (pintype "passive"))
      (node (ref "Q6") (pin "3") (pinfunction "S_3") (pintype "passive"))
      (node (ref "R43") (pin "2") (pinfunction "2_2") (pintype "passive"))
      (node (ref "U12") (pin "3") (pinfunction "VO_3") (pintype "passive"))
    )
    (net (code "4") (name "+12V") (class "Default")
      (node (ref "C11") (pin "1") (pinfunction "1_1") (pintype "passive"))
      (node (ref "C13") (pin "1") (pinfunction "1_1") (pintype "passive"))
      (node (ref "C9") (pin "1") (pinfunction "1_1") (pintype "passive"))
      (node (ref "JP4") (pin "1") (pinfunction "1_1") (pintype "passive"))
      (node (ref "R5") (pin "2") (pinfunction "2_2") (pintype "passive"))
      (node (ref "S5") (pin "1") (pinfunction "O_1") (pintype "passive"))
      (node (ref "U11") (pin "1") (pinfunction "VI_1") (pintype "input"))
      (node (ref "U12") (pin "1") (pinfunction "VI_1") (pintype "input"))
      (node (ref "U13") (pin "1") (pinfunction "VI_1") (pintype "input"))
    )
    (net (code "5") (name "GND") (class "Default")
      (node (ref "C1") (pin "2") (pinfunction "2_2") (pintype "passive"))
      (node (ref "C10") (pin "2") (pinfunction "2_2") (pintype "passive"))
      (node (ref "C11") (pin "2") (pinfunction "2_2") (pintype "passive"))
      (node (ref "C12") (pin "2") (pinfunction "2_2") (pintype "passive"))
      (node (ref "C13") (pin "2") (pinfunction "2_2") (pintype "passive"))
      (node (ref "C14") (pin "2") (pinfunction "2_2") (pintype "passive"))
      (node (ref "C15") (pin "2") (pinfunction "2_2") (pintype "passive"))
      (node (ref "C16") (pin "2") (pinfunction "2_2") (pintype "passive"))
      (node (ref "C17") (pin "2") (pinfunction "2_2") (pintype "passive"))
      (node (ref "C18") (pin "2") (pinfunction "2_2") (pintype "passive"))
      (node (ref "C19") (pin "2") (pinfunction "2_2") (pintype "passive"))
      (node (ref "C2") (pin "2") (pinfunction "2_2") (pintype "passive"))
      (node (ref "C20") (pin "2") (pinfunction "2_2") (pintype "passive"))
      (node (ref "C25") (pin "2") (pinfunction "2_2") (pintype "passive"))
      (node (ref "C27") (pin "2") (pinfunction "2_2") (pintype "passive"))
      (node (ref "C29") (pin "2") (pinfunction "2_2") (pintype "passive"))
      (node (ref "C3") (pin "2") (pinfunction "2_2") (pintype "passive"))
      (node (ref "C30") (pin "2") (pinfunction "2_2") (pintype "passive"))
      (node (ref "C31") (pin "2") (pinfunction "2_2") (pintype "passive"))
      (node (ref "C32") (pin "2") (pinfunction "2_2") (pintype "passive"))
      (node (ref "C34") (pin "2") (pinfunction "2_2") (pintype "passive"))
      (node (ref "C37") (pin "2") (pinfunction "2_2") (pintype "passive"))
      (node (ref "C38") (pin "2") (pinfunction "2_2") (pintype "passive"))
      (node (ref "C4") (pin "-") (pinfunction "-_-") (pintype "passive"))
      (node (ref "C41") (pin "2") (pinfunction "2_2") (pintype "passive"))
      (node (ref "C42") (pin "2") (pinfunction "2_2") (pintype "passive"))
      (node (ref "C43") (pin "2") (pinfunction "2_2") (pintype "passive"))
      (node (ref "C44") (pin "2") (pinfunction "2_2") (pintype "passive"))
      (node (ref "C5") (pin "-") (pinfunction "-_-") (pintype "passive"))
      (node (ref "C6") (pin "-") (pinfunction "-_-") (pintype "passive"))
      (node (ref "C7") (pin "-") (pinfunction "-_-") (pintype "passive"))
      (node (ref "C8") (pin "-") (pinfunction "-_-") (pintype "passive"))
      (node (ref "C9") (pin "2") (pinfunction "2_2") (pintype "passive"))
      (node (ref "D4") (pin "A") (pinfunction "A_A") (pintype "passive"))
      (node (ref "J1") (pin "-") (pinfunction "-_-") (pintype "passive"))
      (node (ref "J10") (pin "21") (pinfunction "KL_21") (pintype "passive"))
      (node (ref "J10") (pin "22") (pinfunction "KL_22") (pintype "passive"))
      (node (ref "J10") (pin "23") (pinfunction "KL_23") (pintype "passive"))
      (node (ref "J10") (pin "24") (pinfunction "KL_24") (pintype "passive"))
      (node (ref "J11") (pin "21") (pinfunction "KL_21") (pintype "passive"))
      (node (ref "J11") (pin "22") (pinfunction "KL_22") (pintype "passive"))
      (node (ref "J11") (pin "23") (pinfunction "KL_23") (pintype "passive"))
      (node (ref "J11") (pin "24") (pinfunction "KL_24") (pintype "passive"))
      (node (ref "J2") (pin "1") (pinfunction "1_1") (pintype "passive"))
      (node (ref "J3") (pin "1") (pinfunction "1_1") (pintype "passive"))
      (node (ref "J4") (pin "1") (pinfunction "1_1") (pintype "passive"))
      (node (ref "J5") (pin "1") (pinfunction "1_1") (pintype "passive"))
      (node (ref "J8") (pin "GND@1") (pinfunction "GNDBREAK_GND@1") (pintype "bidirectional"))
      (node (ref "J8") (pin "GND@2") (pinfunction "GND_GND@2") (pintype "bidirectional"))
      (node (ref "J9") (pin "4") (pinfunction "4_4") (pintype "passive"))
      (node (ref "JP1") (pin "6") (pinfunction "S_6") (pintype "passive"))
      (node (ref "JP2") (pin "2") (pinfunction "2_2") (pintype "passive"))
      (node (ref "JP2") (pin "3") (pinfunction "3_3") (pintype "passive"))
      (node (ref "JP3") (pin "2") (pinfunction "2_2") (pintype "passive"))
      (node (ref "JP4") (pin "2") (pinfunction "2_2") (pintype "passive"))
      (node (ref "LCD1") (pin "1") (pinfunction "VSS_1") (pintype "power_in"))
      (node (ref "LED4") (pin "K") (pinfunction "C_K") (pintype "passive"))
      (node (ref "Q7") (pin "3") (pinfunction "E_3") (pintype "passive"))
      (node (ref "Q8") (pin "3") (pinfunction "E_3") (pintype "passive"))
      (node (ref "R10") (pin "1") (pinfunction "1_1") (pintype "passive"))
      (node (ref "R19") (pin "1") (pinfunction "1_1") (pintype "passive"))
      (node (ref "R2") (pin "1") (pinfunction "1_1") (pintype "passive"))
      (node (ref "R20") (pin "1") (pinfunction "1_1") (pintype "passive"))
      (node (ref "R21") (pin "1") (pinfunction "1_1") (pintype "passive"))
      (node (ref "R22") (pin "1") (pinfunction "1_1") (pintype "passive"))
      (node (ref "R24") (pin "2") (pinfunction "2_2") (pintype "passive"))
      (node (ref "R27") (pin "2") (pinfunction "2_2") (pintype "passive"))
      (node (ref "R28") (pin "2") (pinfunction "2_2") (pintype "passive"))
      (node (ref "R29") (pin "2") (pinfunction "2_2") (pintype "passive"))
      (node (ref "R30") (pin "1") (pinfunction "1_1") (pintype "passive"))
      (node (ref "R33") (pin "1") (pinfunction "1_1") (pintype "passive"))
      (node (ref "R35") (pin "1") (pinfunction "1_1") (pintype "passive"))
      (node (ref "R37") (pin "1") (pinfunction "1_1") (pintype "passive"))
      (node (ref "R4") (pin "1") (pinfunction "1_1") (pintype "passive"))
      (node (ref "R40") (pin "1") (pinfunction "1_1") (pintype "passive"))
      (node (ref "R44") (pin "1") (pinfunction "1_1") (pintype "passive"))
      (node (ref "R46") (pin "1") (pinfunction "1_1") (pintype "passive"))
      (node (ref "R48") (pin "1") (pinfunction "1_1") (pintype "passive"))
      (node (ref "R51") (pin "1") (pinfunction "1_1") (pintype "passive"))
      (node (ref "R58") (pin "1") (pinfunction "1_1") (pintype "passive"))
      (node (ref "R59") (pin "2") (pinfunction "2_2") (pintype "passive"))
      (node (ref "R6") (pin "1") (pinfunction "1_1") (pintype "passive"))
      (node (ref "S1") (pin "3") (pinfunction "P_3") (pintype "passive"))
      (node (ref "S1") (pin "4") (pinfunction "P_4") (pintype "passive"))
      (node (ref "S2") (pin "3") (pinfunction "P_3") (pintype "passive"))
      (node (ref "S2") (pin "4") (pinfunction "P_4") (pintype "passive"))
      (node (ref "S3") (pin "3") (pinfunction "P_3") (pintype "passive"))
      (node (ref "S3") (pin "4") (pinfunction "P_4") (pintype "passive"))
      (node (ref "S4") (pin "3") (pinfunction "P_3") (pintype "passive"))
      (node (ref "S4") (pin "4") (pinfunction "P_4") (pintype "passive"))
      (node (ref "S5") (pin "B") (pinfunction "B_B") (pintype "passive"))
      (node (ref "S5") (pin "B1") (pinfunction "B1_B1") (pintype "passive"))
      (node (ref "U1") (pin "11") (pinfunction "GND_11") (pintype "power_in"))
      (node (ref "U1") (pin "31") (pinfunction "GND_31") (pintype "power_in"))
      (node (ref "U10") (pin "4") (pinfunction "V-_4") (pintype "power_in"))
      (node (ref "U11") (pin "2") (pinfunction "GND_2") (pintype "passive"))
      (node (ref "U12") (pin "2") (pinfunction "GND_2") (pintype "passive"))
      (node (ref "U13") (pin "2") (pinfunction "GND_2") (pintype "passive"))
      (node (ref "U2") (pin "11") (pinfunction "V-_11") (pintype "power_in"))
      (node (ref "U3") (pin "7") (pinfunction "VSS_7") (pintype "power_in"))
      (node (ref "U4") (pin "4") (pinfunction "V-_4") (pintype "power_in"))
      (node (ref "U4") (pin "5") (pinfunction "+IN_5") (pintype "input"))
      (node (ref "U5") (pin "2") (pinfunction "~{ON}/OFF_2") (pintype "input"))
      (node (ref "U5") (pin "3") (pinfunction "GND_3") (pintype "power_in"))
      (node (ref "U8A") (pin "1") (pinfunction "GND_1") (pintype "bidirectional"))
      (node (ref "U8B") (pin "7") (pinfunction "7_7") (pintype "passive"))
      (node (ref "U9") (pin "15") (pinfunction "GND_15") (pintype "power_in"))
      (node (ref "VR1") (pin "1") (pinfunction "A_1") (pintype "passive"))
      (node (ref "VR1") (pin "CHASSIS2") (pinfunction "P$1_CHASSIS2") (pintype "passive"))
      (node (ref "VR2") (pin "1") (pinfunction "A_1") (pintype "passive"))
      (node (ref "VR2") (pin "CHASSIS2") (pinfunction "P$1_CHASSIS2") (pintype "passive"))
      (node (ref "VR3") (pin "1") (pinfunction "A_1") (pintype "passive"))
      (node (ref "VR3") (pin "1B") (pinfunction "A_1B") (pintype "passive"))
      (node (ref "VR3") (pin "CHASSIS1") (pinfunction "P$1_CHASSIS1") (pintype "passive"))
      (node (ref "VR3") (pin "CHASSIS2") (pinfunction "P$1_CHASSIS2") (pintype "passive"))
      (node (ref "VR4") (pin "A") (pinfunction "A_A") (pintype "passive"))
    )
    (net (code "6") (name "Net-(C20-Pad1)") (class "Default")
      (node (ref "C20") (pin "1") (pinfunction "1_1") (pintype "passive"))
      (node (ref "R7") (pin "2") (pinfunction "2_2") (pintype "passive"))
      (node (ref "R8") (pin "1") (pinfunction "1_1") (pintype "passive"))
    )
    (net (code "7") (name "Net-(C21-Pad1)") (class "Default")
      (node (ref "C21") (pin "1") (pinfunction "1_1") (pintype "passive"))
      (node (ref "J4") (pin "2") (pinfunction "2_2") (pintype "passive"))
      (node (ref "J4") (pin "5") (pinfunction "5_5") (pintype "passive"))
      (node (ref "R7") (pin "1") (pinfunction "1_1") (pintype "passive"))
    )
    (net (code "8") (name "Net-(C22-Pad2)") (class "Default")
      (node (ref "C22") (pin "2") (pinfunction "2_2") (pintype "passive"))
      (node (ref "R13") (pin "2") (pinfunction "2_2") (pintype "passive"))
    )
    (net (code "9") (name "Net-(C23-Pad1)") (class "Default")
      (node (ref "C23") (pin "1") (pinfunction "1_1") (pintype "passive"))
      (node (ref "R14") (pin "2") (pinfunction "2_2") (pintype "passive"))
    )
    (net (code "10") (name "Net-(C24-Pad1)") (class "Default")
      (node (ref "C24") (pin "1") (pinfunction "1_1") (pintype "passive"))
      (node (ref "R15") (pin "2") (pinfunction "2_2") (pintype "passive"))
    )
    (net (code "11") (name "Net-(C43-Pad1)") (class "Default")
      (node (ref "C43") (pin "1") (pinfunction "1_1") (pintype "passive"))
      (node (ref "R11") (pin "1") (pinfunction "1_1") (pintype "passive"))
    )
    (net (code "12") (name "Net-(F1-Pad1)") (class "Default")
      (node (ref "F1") (pin "1") (pinfunction "1_1") (pintype "passive"))
      (node (ref "J1") (pin "+") (pinfunction "+_+") (pintype "passive"))
    )
    (net (code "13") (name "Net-(J2-Pad2)") (class "Default")
      (node (ref "J2") (pin "2") (pinfunction "2_2") (pintype "passive"))
      (node (ref "R18") (pin "1") (pinfunction "1_1") (pintype "passive"))
      (node (ref "R19") (pin "2") (pinfunction "2_2") (pintype "passive"))
    )
    (net (code "14") (name "Net-(J2-Pad5)") (class "Default")
      (node (ref "J2") (pin "5") (pinfunction "5_5") (pintype "passive"))
      (node (ref "R62") (pin "1") (pinfunction "1_1") (pintype "passive"))
    )
    (net (code "15") (name "Net-(J5-Pad2)") (class "Default")
      (node (ref "J5") (pin "2") (pinfunction "2_2") (pintype "passive"))
      (node (ref "R15") (pin "1") (pinfunction "1_1") (pintype "passive"))
    )
    (net (code "16") (name "Net-(J5-Pad3)") (class "Default")
      (node (ref "J5") (pin "3") (pinfunction "3_3") (pintype "passive"))
      (node (ref "JP2") (pin "4") (pinfunction "4_4") (pintype "passive"))
    )
    (net (code "17") (name "Net-(J5-Pad4)") (class "Default")
      (node (ref "J5") (pin "4") (pinfunction "4_4") (pintype "passive"))
      (node (ref "JP2") (pin "1") (pinfunction "1_1") (pintype "passive"))
    )
    (net (code "18") (name "Net-(J5-Pad5)") (class "Default")
      (node (ref "J5") (pin "5") (pinfunction "5_5") (pintype "passive"))
      (node (ref "R14") (pin "1") (pinfunction "1_1") (pintype "passive"))
    )
    (net (code "19") (name "Net-(J6-Pad1)") (class "Default")
      (node (ref "J6") (pin "1") (pinfunction "1_1") (pintype "passive"))
      (node (ref "TR1") (pin "1") (pinfunction "1_1") (pintype "passive"))
    )
    (net (code "20") (name "Net-(J6-Pad2)") (class "Default")
      (node (ref "J6") (pin "2") (pinfunction "2_2") (pintype "passive"))
      (node (ref "JP6") (pin "2") (pinfunction "2_2") (pintype "passive"))
    )
    (net (code "21") (name "Net-(J6-Pad5)") (class "Default")
      (node (ref "J6") (pin "5") (pinfunction "5_5") (pintype "passive"))
      (node (ref "TR1") (pin "3") (pinfunction "3_3") (pintype "passive"))
    )
    (net (code "22") (name "Net-(J7-Pad1)") (class "Default")
      (node (ref "J7") (pin "1") (pinfunction "1_1") (pintype "passive"))
      (node (ref "TR2") (pin "1") (pinfunction "1_1") (pintype "passive"))
    )
    (net (code "23") (name "Net-(J7-Pad2)") (class "Default")
      (node (ref "J7") (pin "2") (pinfunction "2_2") (pintype "passive"))
      (node (ref "JP7") (pin "2") (pinfunction "2_2") (pintype "passive"))
    )
    (net (code "24") (name "Net-(J7-Pad5)") (class "Default")
      (node (ref "J7") (pin "5") (pinfunction "5_5") (pintype "passive"))
      (node (ref "TR2") (pin "3") (pinfunction "3_3") (pintype "passive"))
    )
    (net (code "25") (name "Net-(J9-Pad2)") (class "Default")
      (node (ref "J9") (pin "2") (pinfunction "2_2") (pintype "passive"))
      (node (ref "R58") (pin "2") (pinfunction "2_2") (pintype "passive"))
      (node (ref "R9") (pin "1") (pinfunction "1_1") (pintype "passive"))
    )
    (net (code "26") (name "Net-(J10A-KL)") (class "Default")
      (node (ref "J10") (pin "1") (pinfunction "KL_1") (pintype "passive"))
      (node (ref "VR3") (pin "3") (pinfunction "E_3") (pintype "passive"))
    )
    (net (code "27") (name "Net-(J10C-KL)") (class "Default")
      (node (ref "J10") (pin "11") (pinfunction "KL_11") (pintype "passive"))
      (node (ref "VR2") (pin "2") (pinfunction "S_2") (pintype "passive"))
    )
    (net (code "28") (name "Net-(J10I-KL)") (class "Default")
      (node (ref "J10") (pin "17") (pinfunction "KL_17") (pintype "passive"))
      (node (ref "LED3") (pin "A") (pinfunction "A_A") (pintype "passive"))
    )
    (net (code "29") (name "Net-(J10R-KL)") (class "Default")
      (node (ref "J10") (pin "3") (pinfunction "KL_3") (pintype "passive"))
      (node (ref "VR3") (pin "3B") (pinfunction "E_3B") (pintype "passive"))
    )
    (net (code "30") (name "Net-(J10T-KL)") (class "Default")
      (node (ref "J10") (pin "5") (pinfunction "KL_5") (pintype "passive"))
      (node (ref "VR3") (pin "2") (pinfunction "S_2") (pintype "passive"))
    )
    (net (code "31") (name "Net-(J10V-KL)") (class "Default")
      (node (ref "J10") (pin "7") (pinfunction "KL_7") (pintype "passive"))
      (node (ref "VR3") (pin "2B") (pinfunction "S_2B") (pintype "passive"))
    )
    (net (code "32") (name "Net-(J10X-KL)") (class "Default")
      (node (ref "J10") (pin "9") (pinfunction "KL_9") (pintype "passive"))
      (node (ref "VR1") (pin "2") (pinfunction "S_2") (pintype "passive"))
    )
    (net (code "33") (name "Net-(JP6-Pad1)") (class "Default")
      (node (ref "JP6") (pin "1") (pinfunction "1_1") (pintype "passive"))
      (node (ref "TR1") (pin "2") (pinfunction "2_2") (pintype "passive"))
    )
    (net (code "34") (name "Net-(JP7-Pad1)") (class "Default")
      (node (ref "JP7") (pin "1") (pinfunction "1_1") (pintype "passive"))
      (node (ref "TR2") (pin "2") (pinfunction "2_2") (pintype "passive"))
    )
    (net (code "35") (name "Net-(LCD1-A)") (class "Default")
      (node (ref "LCD1") (pin "15") (pinfunction "A_15") (pintype "input"))
      (node (ref "R55") (pin "1") (pinfunction "1_1") (pintype "passive"))
    )
    (net (code "36") (name "Net-(LCD1-K)") (class "Default")
      (node (ref "LCD1") (pin "16") (pinfunction "K_16") (pintype "input"))
      (node (ref "Q8") (pin "1") (pinfunction "C_1") (pintype "passive"))
    )
    (net (code "37") (name "Net-(LCD1-VO)") (class "Default")
      (node (ref "LCD1") (pin "3") (pinfunction "VO_3") (pintype "input"))
      (node (ref "VR4") (pin "S") (pinfunction "S_S") (pintype "passive"))
    )
    (net (code "38") (name "Net-(LED1-PadA)") (class "Default")
      (node (ref "LED1") (pin "A") (pinfunction "A_A") (pintype "passive"))
      (node (ref "R54") (pin "1") (pinfunction "1_1") (pintype "passive"))
    )
    (net (code "39") (name "Net-(LED2-PadA)") (class "Default")
      (node (ref "LED2") (pin "A") (pinfunction "A_A") (pintype "passive"))
      (node (ref "R53") (pin "1") (pinfunction "1_1") (pintype "passive"))
    )
    (net (code "40") (name "Net-(LED3-C)") (class "Default")
      (node (ref "LED3") (pin "K") (pinfunction "C_K") (pintype "passive"))
      (node (ref "R59") (pin "1") (pinfunction "1_1") (pintype "passive"))
    )
    (net (code "41") (name "Net-(LED4-PadA)") (class "Default")
      (node (ref "LED4") (pin "A") (pinfunction "A_A") (pintype "passive"))
      (node (ref "R60") (pin "1") (pinfunction "1_1") (pintype "passive"))
    )
    (net (code "42") (name "Net-(Q1-D)") (class "Default")
      (node (ref "Q1") (pin "2") (pinfunction "D_2") (pintype "passive"))
      (node (ref "TR1") (pin "4") (pinfunction "4_4") (pintype "passive"))
    )
    (net (code "43") (name "Net-(Q1-G)") (class "Default")
      (node (ref "Q1") (pin "1") (pinfunction "G_1") (pintype "passive"))
      (node (ref "R38") (pin "2") (pinfunction "2_2") (pintype "passive"))
    )
    (net (code "44") (name "Net-(Q2-D)") (class "Default")
      (node (ref "Q2") (pin "2") (pinfunction "D_2") (pintype "passive"))
      (node (ref "TR1") (pin "6") (pinfunction "6_6") (pintype "passive"))
    )
    (net (code "45") (name "Net-(Q2-G)") (class "Default")
      (node (ref "Q2") (pin "1") (pinfunction "G_1") (pintype "passive"))
      (node (ref "R41") (pin "2") (pinfunction "2_2") (pintype "passive"))
    )
    (net (code "46") (name "Net-(Q3-D)") (class "Default")
      (node (ref "Q3") (pin "2") (pinfunction "D_2") (pintype "passive"))
      (node (ref "TR1") (pin "5") (pinfunction "5_5") (pintype "passive"))
    )
    (net (code "47") (name "Net-(Q3-G)") (class "Default")
      (node (ref "C39") (pin "1") (pinfunction "1_1") (pintype "passive"))
      (node (ref "Q3") (pin "1") (pinfunction "G_1") (pintype "passive"))
      (node (ref "R39") (pin "2") (pinfunction "2_2") (pintype "passive"))
    )
    (net (code "48") (name "Net-(Q4-D)") (class "Default")
      (node (ref "Q4") (pin "2") (pinfunction "D_2") (pintype "passive"))
      (node (ref "TR2") (pin "4") (pinfunction "4_4") (pintype "passive"))
    )
    (net (code "49") (name "Net-(Q4-G)") (class "Default")
      (node (ref "Q4") (pin "1") (pinfunction "G_1") (pintype "passive"))
      (node (ref "R49") (pin "2") (pinfunction "2_2") (pintype "passive"))
    )
    (net (code "50") (name "Net-(Q5-D)") (class "Default")
      (node (ref "Q5") (pin "2") (pinfunction "D_2") (pintype "passive"))
      (node (ref "TR2") (pin "6") (pinfunction "6_6") (pintype "passive"))
    )
    (net (code "51") (name "Net-(Q5-G)") (class "Default")
      (node (ref "Q5") (pin "1") (pinfunction "G_1") (pintype "passive"))
      (node (ref "R52") (pin "2") (pinfunction "2_2") (pintype "passive"))
    )
    (net (code "52") (name "Net-(Q6-D)") (class "Default")
      (node (ref "Q6") (pin "2") (pinfunction "D_2") (pintype "passive"))
      (node (ref "TR2") (pin "5") (pinfunction "5_5") (pintype "passive"))
    )
    (net (code "53") (name "Net-(Q6-G)") (class "Default")
      (node (ref "C40") (pin "1") (pinfunction "1_1") (pintype "passive"))
      (node (ref "Q6") (pin "1") (pinfunction "G_1") (pintype "passive"))
      (node (ref "R50") (pin "2") (pinfunction "2_2") (pintype "passive"))
    )
    (net (code "54") (name "Net-(Q7-B)") (class "Default")
      (node (ref "Q7") (pin "2") (pinfunction "B_2") (pintype "passive"))
      (node (ref "R56") (pin "1") (pinfunction "1_1") (pintype "passive"))
    )
    (net (code "55") (name "Net-(Q7-C)") (class "Default")
      (node (ref "Q7") (pin "1") (pinfunction "C_1") (pintype "passive"))
      (node (ref "Q8") (pin "2") (pinfunction "B_2") (pintype "passive"))
      (node (ref "R57") (pin "2") (pinfunction "2_2") (pintype "passive"))
    )
    (net (code "56") (name "Net-(S5-P)") (class "Default")
      (node (ref "C5") (pin "+") (pinfunction "+_+") (pintype "passive"))
      (node (ref "D1") (pin "C") (pinfunction "C_C") (pintype "passive"))
      (node (ref "D4") (pin "C") (pinfunction "C_C") (pintype "passive"))
      (node (ref "F1") (pin "2") (pinfunction "2_2") (pintype "passive"))
      (node (ref "S5") (pin "2") (pinfunction "P_2") (pintype "passive"))
      (node (ref "S5") (pin "3") (pinfunction "S_3") (pintype "passive"))
    )
    (net (code "57") (name "Net-(U1-(ADC2)PA2)") (class "Default")
      (node (ref "R3") (pin "1") (pinfunction "1_1") (pintype "passive"))
      (node (ref "R4") (pin "2") (pinfunction "2_2") (pintype "passive"))
      (node (ref "U1") (pin "38") (pinfunction "(ADC2)PA2_38") (pintype "bidirectional"))
    )
    (net (code "58") (name "Net-(U1-(ADC3)PA3)") (class "Default")
      (node (ref "R5") (pin "1") (pinfunction "1_1") (pintype "passive"))
      (node (ref "R6") (pin "2") (pinfunction "2_2") (pintype "passive"))
      (node (ref "U1") (pin "37") (pinfunction "(ADC3)PA3_37") (pintype "bidirectional"))
    )
    (net (code "59") (name "Net-(U1-XTAL1)") (class "Default")
      (node (ref "C16") (pin "1") (pinfunction "1_1") (pintype "passive"))
      (node (ref "U1") (pin "13") (pinfunction "XTAL1_13") (pintype "bidirectional"))
      (node (ref "XTAL1") (pin "2") (pinfunction "2_2") (pintype "passive"))
    )
    (net (code "60") (name "Net-(U1-XTAL2)") (class "Default")
      (node (ref "C15") (pin "1") (pinfunction "1_1") (pintype "passive"))
      (node (ref "U1") (pin "12") (pinfunction "XTAL2_12") (pintype "bidirectional"))
      (node (ref "XTAL1") (pin "1") (pinfunction "1_1") (pintype "passive"))
    )
    (net (code "61") (name "Net-(U2A-+IN)") (class "Default")
      (node (ref "C28") (pin "2") (pinfunction "2_2") (pintype "passive"))
      (node (ref "R21") (pin "2") (pinfunction "2_2") (pintype "passive"))
      (node (ref "R62") (pin "2") (pinfunction "2_2") (pintype "passive"))
      (node (ref "U2") (pin "3") (pinfunction "+IN_3") (pintype "input"))
    )
    (net (code "62") (name "Net-(U2A--IN)") (class "Default")
      (node (ref "R24") (pin "1") (pinfunction "1_1") (pintype "passive"))
      (node (ref "R25") (pin "1") (pinfunction "1_1") (pintype "passive"))
      (node (ref "U2") (pin "2") (pinfunction "-IN_2") (pintype "input"))
    )
    (net (code "63") (name "Net-(U2A-OUT)") (class "Default")
      (node (ref "D2") (pin "A") (pinfunction "A_A") (pintype "passive"))
      (node (ref "R25") (pin "2") (pinfunction "2_2") (pintype "passive"))
      (node (ref "U2") (pin "1") (pinfunction "OUT_1") (pintype "output"))
      (node (ref "U2") (pin "12") (pinfunction "+IN_12") (pintype "input"))
    )
    (net (code "64") (name "Net-(U2B-+IN)") (class "Default")
      (node (ref "C26") (pin "2") (pinfunction "2_2") (pintype "passive"))
      (node (ref "R20") (pin "2") (pinfunction "2_2") (pintype "passive"))
      (node (ref "U2") (pin "5") (pinfunction "+IN_5") (pintype "input"))
    )
    (net (code "65") (name "Net-(U2B--IN)") (class "Default")
      (node (ref "R22") (pin "2") (pinfunction "2_2") (pintype "passive"))
      (node (ref "R23") (pin "1") (pinfunction "1_1") (pintype "passive"))
      (node (ref "U2") (pin "6") (pinfunction "-IN_6") (pintype "input"))
    )
    (net (code "66") (name "Net-(U2B-OUT)") (class "Default")
      (node (ref "D3") (pin "A") (pinfunction "A_A") (pintype "passive"))
      (node (ref "R23") (pin "2") (pinfunction "2_2") (pintype "passive"))
      (node (ref "U2") (pin "10") (pinfunction "+IN_10") (pintype "input"))
      (node (ref "U2") (pin "7") (pinfunction "OUT_7") (pintype "output"))
    )
    (net (code "67") (name "Net-(U2C--IN)") (class "Default")
      (node (ref "R26") (pin "1") (pinfunction "1_1") (pintype "passive"))
      (node (ref "R27") (pin "1") (pinfunction "1_1") (pintype "passive"))
      (node (ref "U2") (pin "13") (pinfunction "-IN_13") (pintype "input"))
      (node (ref "U2") (pin "9") (pinfunction "-IN_9") (pintype "input"))
    )
    (net (code "68") (name "Net-(U3A-A)") (class "Default")
      (node (ref "S2") (pin "1") (pinfunction "S_1") (pintype "passive"))
      (node (ref "S2") (pin "2") (pinfunction "S_2") (pintype "passive"))
      (node (ref "U3") (pin "1") (pinfunction "A_1") (pintype "tri_state"))
    )
    (net (code "69") (name "Net-(U3B-A)") (class "Default")
      (node (ref "S4") (pin "1") (pinfunction "S_1") (pintype "passive"))
      (node (ref "S4") (pin "2") (pinfunction "S_2") (pintype "passive"))
      (node (ref "U3") (pin "4") (pinfunction "A_4") (pintype "tri_state"))
    )
    (net (code "70") (name "Net-(U3C-A)") (class "Default")
      (node (ref "S1") (pin "1") (pinfunction "S_1") (pintype "passive"))
      (node (ref "S1") (pin "2") (pinfunction "S_2") (pintype "passive"))
      (node (ref "U3") (pin "8") (pinfunction "A_8") (pintype "tri_state"))
    )
    (net (code "71") (name "Net-(U3D-A)") (class "Default")
      (node (ref "S3") (pin "1") (pinfunction "S_1") (pintype "passive"))
      (node (ref "S3") (pin "2") (pinfunction "S_2") (pintype "passive"))
      (node (ref "U3") (pin "11") (pinfunction "A_11") (pintype "tri_state"))
    )
    (net (code "72") (name "Net-(U4A-+IN)") (class "Default")
      (node (ref "C21") (pin "2") (pinfunction "2_2") (pintype "passive"))
      (node (ref "R10") (pin "2") (pinfunction "2_2") (pintype "passive"))
      (node (ref "R61") (pin "1") (pinfunction "1_1") (pintype "passive"))
      (node (ref "U4") (pin "3") (pinfunction "+IN_3") (pintype "input"))
    )
    (net (code "73") (name "Net-(U4A--IN)") (class "Default")
      (node (ref "R11") (pin "2") (pinfunction "2_2") (pintype "passive"))
      (node (ref "R12") (pin "1") (pinfunction "1_1") (pintype "passive"))
      (node (ref "U4") (pin "2") (pinfunction "-IN_2") (pintype "input"))
    )
    (net (code "74") (name "Net-(U4A-OUT)") (class "Default")
      (node (ref "R12") (pin "2") (pinfunction "2_2") (pintype "passive"))
      (node (ref "R13") (pin "1") (pinfunction "1_1") (pintype "passive"))
      (node (ref "U4") (pin "1") (pinfunction "OUT_1") (pintype "output"))
      (node (ref "U4") (pin "6") (pinfunction "-IN_6") (pintype "input"))
    )
    (net (code "75") (name "Net-(U5-ADJ)") (class "Default")
      (node (ref "R1") (pin "1") (pinfunction "1_1") (pintype "passive"))
      (node (ref "R2") (pin "2") (pinfunction "2_2") (pintype "passive"))
      (node (ref "U5") (pin "1") (pinfunction "ADJ_1") (pintype "passive"))
    )
    (net (code "76") (name "Net-(U5-OUT)") (class "Default")
      (node (ref "C3") (pin "1") (pinfunction "1_1") (pintype "passive"))
      (node (ref "C4") (pin "+") (pinfunction "+_+") (pintype "passive"))
      (node (ref "D1") (pin "A") (pinfunction "A_A") (pintype "passive"))
      (node (ref "R1") (pin "2") (pinfunction "2_2") (pintype "passive"))
      (node (ref "U5") (pin "5") (pinfunction "OUT_5") (pintype "passive"))
    )
    (net (code "77") (name "Net-(U8A-OUTA)") (class "Default")
      (node (ref "R31") (pin "1") (pinfunction "1_1") (pintype "passive"))
      (node (ref "U8A") (pin "2") (pinfunction "OUTA_2") (pintype "bidirectional"))
      (node (ref "U8B") (pin "5") (pinfunction "5_5") (pintype "passive"))
    )
    (net (code "78") (name "Net-(U8A-OUTB)") (class "Default")
      (node (ref "R42") (pin "1") (pinfunction "1_1") (pintype "passive"))
      (node (ref "U8A") (pin "7") (pinfunction "OUTB_7") (pintype "bidirectional"))
      (node (ref "U8B") (pin "8") (pinfunction "8_8") (pintype "passive"))
    )
    (net (code "79") (name "Net-(U9A-C1+)") (class "Default")
      (node (ref "C35") (pin "1") (pinfunction "1_1") (pintype "passive"))
      (node (ref "U9") (pin "1") (pinfunction "C1+_1") (pintype "bidirectional"))
    )
    (net (code "80") (name "Net-(U9A-C1-)") (class "Default")
      (node (ref "C35") (pin "2") (pinfunction "2_2") (pintype "passive"))
      (node (ref "U9") (pin "3") (pinfunction "C1-_3") (pintype "bidirectional"))
    )
    (net (code "81") (name "Net-(U9A-C2+)") (class "Default")
      (node (ref "C36") (pin "1") (pinfunction "1_1") (pintype "passive"))
      (node (ref "U9") (pin "4") (pinfunction "C2+_4") (pintype "bidirectional"))
    )
    (net (code "82") (name "Net-(U9A-C2-)") (class "Default")
      (node (ref "C36") (pin "2") (pinfunction "2_2") (pintype "passive"))
      (node (ref "U9") (pin "5") (pinfunction "C2-_5") (pintype "bidirectional"))
    )
    (net (code "83") (name "Net-(U9A-R1IN)") (class "Default")
      (node (ref "J3") (pin "2") (pinfunction "2_2") (pintype "passive"))
      (node (ref "U9") (pin "13") (pinfunction "R1IN_13") (pintype "input"))
    )
    (net (code "84") (name "Net-(U9A-R2IN)") (class "Default")
      (node (ref "J3") (pin "4") (pinfunction "4_4") (pintype "passive"))
      (node (ref "U9") (pin "8") (pinfunction "R2IN_8") (pintype "input"))
    )
    (net (code "85") (name "Net-(U9A-R2OUT)") (class "Default")
      (node (ref "R9") (pin "2") (pinfunction "2_2") (pintype "passive"))
      (node (ref "U9") (pin "9") (pinfunction "R2OUT_9") (pintype "output"))
    )
    (net (code "86") (name "Net-(U9A-T1OUT)") (class "Default")
      (node (ref "J3") (pin "5") (pinfunction "5_5") (pintype "passive"))
      (node (ref "U9") (pin "14") (pinfunction "T1OUT_14") (pintype "output"))
    )
    (net (code "87") (name "Net-(U9A-T2IN)") (class "Default")
      (node (ref "J9") (pin "3") (pinfunction "3_3") (pintype "passive"))
      (node (ref "U9") (pin "10") (pinfunction "T2IN_10") (pintype "input"))
    )
    (net (code "88") (name "Net-(U9A-T2OUT)") (class "Default")
      (node (ref "J3") (pin "3") (pinfunction "3_3") (pintype "passive"))
      (node (ref "U9") (pin "7") (pinfunction "T2OUT_7") (pintype "output"))
    )
    (net (code "89") (name "Net-(U9A-V+)") (class "Default")
      (node (ref "C33") (pin "2") (pinfunction "2_2") (pintype "passive"))
      (node (ref "U9") (pin "2") (pinfunction "V+_2") (pintype "bidirectional"))
    )
    (net (code "90") (name "Net-(U9A-V-)") (class "Default")
      (node (ref "C34") (pin "1") (pinfunction "1_1") (pintype "passive"))
      (node (ref "U9") (pin "6") (pinfunction "V-_6") (pintype "bidirectional"))
    )
    (net (code "91") (name "Net-(U10A-+IN)") (class "Default")
      (node (ref "R31") (pin "2") (pinfunction "2_2") (pintype "passive"))
      (node (ref "R32") (pin "1") (pinfunction "1_1") (pintype "passive"))
      (node (ref "R33") (pin "2") (pinfunction "2_2") (pintype "passive"))
      (node (ref "U10") (pin "3") (pinfunction "+IN_3") (pintype "input"))
    )
    (net (code "92") (name "Net-(U10A--IN)") (class "Default")
      (node (ref "R34") (pin "1") (pinfunction "1_1") (pintype "passive"))
      (node (ref "R35") (pin "2") (pinfunction "2_2") (pintype "passive"))
      (node (ref "R36") (pin "1") (pinfunction "1_1") (pintype "passive"))
      (node (ref "U10") (pin "2") (pinfunction "-IN_2") (pintype "input"))
    )
    (net (code "93") (name "Net-(U10A-OUT)") (class "Default")
      (node (ref "R36") (pin "2") (pinfunction "2_2") (pintype "passive"))
      (node (ref "R39") (pin "1") (pinfunction "1_1") (pintype "passive"))
      (node (ref "U10") (pin "1") (pinfunction "OUT_1") (pintype "output"))
    )
    (net (code "94") (name "Net-(U10B-+IN)") (class "Default")
      (node (ref "R42") (pin "2") (pinfunction "2_2") (pintype "passive"))
      (node (ref "R43") (pin "1") (pinfunction "1_1") (pintype "passive"))
      (node (ref "R44") (pin "2") (pinfunction "2_2") (pintype "passive"))
      (node (ref "U10") (pin "5") (pinfunction "+IN_5") (pintype "input"))
    )
    (net (code "95") (name "Net-(U10B--IN)") (class "Default")
      (node (ref "R45") (pin "1") (pinfunction "1_1") (pintype "passive"))
      (node (ref "R46") (pin "2") (pinfunction "2_2") (pintype "passive"))
      (node (ref "R47") (pin "1") (pinfunction "1_1") (pintype "passive"))
      (node (ref "U10") (pin "6") (pinfunction "-IN_6") (pintype "input"))
    )
    (net (code "96") (name "Net-(U10B-OUT)") (class "Default")
      (node (ref "R47") (pin "2") (pinfunction "2_2") (pintype "passive"))
      (node (ref "R50") (pin "1") (pinfunction "1_1") (pintype "passive"))
      (node (ref "U10") (pin "7") (pinfunction "OUT_7") (pintype "output"))
    )
    (net (code "97") (name "PA0") (class "Default")
      (node (ref "Q1") (pin "3") (pinfunction "S_3") (pintype "passive"))
      (node (ref "Q2") (pin "3") (pinfunction "S_3") (pintype "passive"))
      (node (ref "Q4") (pin "3") (pinfunction "S_3") (pintype "passive"))
      (node (ref "Q5") (pin "3") (pinfunction "S_3") (pintype "passive"))
      (node (ref "R30") (pin "2") (pinfunction "2_2") (pintype "passive"))
      (node (ref "U1") (pin "40") (pinfunction "(ADC0)PA0_40") (pintype "bidirectional"))
    )
    (net (code "98") (name "PA1") (class "Default")
      (node (ref "C25") (pin "1") (pinfunction "1_1") (pintype "passive"))
      (node (ref "C26") (pin "1") (pinfunction "1_1") (pintype "passive"))
      (node (ref "J11") (pin "5") (pinfunction "KL_5") (pintype "passive"))
      (node (ref "U1") (pin "39") (pinfunction "(ADC1)PA1_39") (pintype "bidirectional"))
    )
    (net (code "99") (name "PA4") (class "Default")
      (node (ref "J11") (pin "9") (pinfunction "KL_9") (pintype "passive"))
      (node (ref "U1") (pin "36") (pinfunction "(ADC4)PA4_36") (pintype "bidirectional"))
    )
    (net (code "100") (name "PA5") (class "Default")
      (node (ref "J11") (pin "11") (pinfunction "KL_11") (pintype "passive"))
      (node (ref "U1") (pin "35") (pinfunction "(ADC5)PA5_35") (pintype "bidirectional"))
    )
    (net (code "101") (name "PA6") (class "Default")
      (node (ref "C31") (pin "1") (pinfunction "1_1") (pintype "passive"))
      (node (ref "D2") (pin "C") (pinfunction "C_C") (pintype "passive"))
      (node (ref "R29") (pin "1") (pinfunction "1_1") (pintype "passive"))
      (node (ref "U1") (pin "34") (pinfunction "(ADC6)PA6_34") (pintype "bidirectional"))
    )
    (net (code "102") (name "PA7") (class "Default")
      (node (ref "C30") (pin "1") (pinfunction "1_1") (pintype "passive"))
      (node (ref "D3") (pin "C") (pinfunction "C_C") (pintype "passive"))
      (node (ref "R28") (pin "1") (pinfunction "1_1") (pintype "passive"))
      (node (ref "U1") (pin "33") (pinfunction "(ADC7)PA7_33") (pintype "bidirectional"))
    )
    (net (code "103") (name "PB0") (class "Default")
      (node (ref "R48") (pin "2") (pinfunction "2_2") (pintype "passive"))
      (node (ref "R49") (pin "1") (pinfunction "1_1") (pintype "passive"))
      (node (ref "U1") (pin "1") (pinfunction "(T0/XCK)PB0_1") (pintype "bidirectional"))
    )
    (net (code "104") (name "PB1") (class "Default")
      (node (ref "R51") (pin "2") (pinfunction "2_2") (pintype "passive"))
      (node (ref "R52") (pin "1") (pinfunction "1_1") (pintype "passive"))
      (node (ref "U1") (pin "2") (pinfunction "(T1)PB1_2") (pintype "bidirectional"))
    )
    (net (code "105") (name "PB2") (class "Default")
      (node (ref "R37") (pin "2") (pinfunction "2_2") (pintype "passive"))
      (node (ref "R38") (pin "1") (pinfunction "1_1") (pintype "passive"))
      (node (ref "U1") (pin "3") (pinfunction "(AIN0/INT2)PB2_3") (pintype "bidirectional"))
    )
    (net (code "106") (name "PB3") (class "Default")
      (node (ref "R40") (pin "2") (pinfunction "2_2") (pintype "passive"))
      (node (ref "R41") (pin "1") (pinfunction "1_1") (pintype "passive"))
      (node (ref "U1") (pin "4") (pinfunction "(AIN1/OC0)PB3_4") (pintype "bidirectional"))
    )
    (net (code "107") (name "PB5") (class "Default")
      (node (ref "JP1") (pin "4") (pinfunction "S_4") (pintype "passive"))
      (node (ref "U1") (pin "6") (pinfunction "(MOSI)PB5_6") (pintype "bidirectional"))
      (node (ref "U8A") (pin "4") (pinfunction "DIN_4") (pintype "bidirectional"))
      (node (ref "U8B") (pin "3") (pinfunction "3_3") (pintype "passive"))
    )
    (net (code "108") (name "PB6") (class "Default")
      (node (ref "JP1") (pin "1") (pinfunction "S_1") (pintype "passive"))
      (node (ref "U1") (pin "7") (pinfunction "(MISO)PB6_7") (pintype "bidirectional"))
    )
    (net (code "109") (name "PB7") (class "Default")
      (node (ref "JP1") (pin "3") (pinfunction "S_3") (pintype "passive"))
      (node (ref "U1") (pin "8") (pinfunction "(SCK)PB7_8") (pintype "bidirectional"))
      (node (ref "U8A") (pin "5") (pinfunction "SCLK_5") (pintype "bidirectional"))
      (node (ref "U8B") (pin "2") (pinfunction "2_2") (pintype "passive"))
    )
    (net (code "110") (name "PC0") (class "Default")
      (node (ref "J10") (pin "2") (pinfunction "KL_2") (pintype "passive"))
      (node (ref "J11") (pin "2") (pinfunction "KL_2") (pintype "passive"))
      (node (ref "U1") (pin "22") (pinfunction "(SCL)PC0_22") (pintype "bidirectional"))
      (node (ref "U3") (pin "12") (pinfunction "C_12") (pintype "input"))
      (node (ref "U3") (pin "13") (pinfunction "C_13") (pintype "input"))
      (node (ref "U3") (pin "5") (pinfunction "C_5") (pintype "input"))
      (node (ref "U3") (pin "6") (pinfunction "C_6") (pintype "input"))
    )
    (net (code "111") (name "PC1") (class "Default")
      (node (ref "J10") (pin "4") (pinfunction "KL_4") (pintype "passive"))
      (node (ref "J11") (pin "4") (pinfunction "KL_4") (pintype "passive"))
      (node (ref "LCD1") (pin "5") (pinfunction "RW_5") (pintype "input"))
      (node (ref "U1") (pin "23") (pinfunction "(SDA)PC1_23") (pintype "bidirectional"))
    )
    (net (code "112") (name "PC2") (class "Default")
      (node (ref "J10") (pin "6") (pinfunction "KL_6") (pintype "passive"))
      (node (ref "J11") (pin "6") (pinfunction "KL_6") (pintype "passive"))
      (node (ref "LCD1") (pin "6") (pinfunction "E_6") (pintype "input"))
      (node (ref "U1") (pin "24") (pinfunction "(TCK)PC2_24") (pintype "bidirectional"))
    )
    (net (code "113") (name "PC3") (class "Default")
      (node (ref "J10") (pin "8") (pinfunction "KL_8") (pintype "passive"))
      (node (ref "J11") (pin "8") (pinfunction "KL_8") (pintype "passive"))
      (node (ref "LCD1") (pin "4") (pinfunction "RS_4") (pintype "input"))
      (node (ref "U1") (pin "25") (pinfunction "(TMS)PC3_25") (pintype "bidirectional"))
    )
    (net (code "114") (name "PC4") (class "Default")
      (node (ref "J10") (pin "10") (pinfunction "KL_10") (pintype "passive"))
      (node (ref "J11") (pin "10") (pinfunction "KL_10") (pintype "passive"))
      (node (ref "LCD1") (pin "11") (pinfunction "DB4_11") (pintype "bidirectional"))
      (node (ref "U1") (pin "26") (pinfunction "(TDO)PC4_26") (pintype "bidirectional"))
      (node (ref "U3") (pin "10") (pinfunction "B_10") (pintype "tri_state"))
    )
    (net (code "115") (name "PC5") (class "Default")
      (node (ref "J10") (pin "12") (pinfunction "KL_12") (pintype "passive"))
      (node (ref "J11") (pin "12") (pinfunction "KL_12") (pintype "passive"))
      (node (ref "LCD1") (pin "12") (pinfunction "DB5_12") (pintype "bidirectional"))
      (node (ref "U1") (pin "27") (pinfunction "(TDI)PC5_27") (pintype "bidirectional"))
      (node (ref "U3") (pin "9") (pinfunction "B_9") (pintype "tri_state"))
    )
    (net (code "116") (name "PC6") (class "Default")
      (node (ref "J10") (pin "14") (pinfunction "KL_14") (pintype "passive"))
      (node (ref "J11") (pin "14") (pinfunction "KL_14") (pintype "passive"))
      (node (ref "LCD1") (pin "13") (pinfunction "DB6_13") (pintype "bidirectional"))
      (node (ref "U1") (pin "28") (pinfunction "(TOSC1)PC6_28") (pintype "bidirectional"))
      (node (ref "U3") (pin "3") (pinfunction "B_3") (pintype "tri_state"))
    )
    (net (code "117") (name "PC7") (class "Default")
      (node (ref "J10") (pin "16") (pinfunction "KL_16") (pintype "passive"))
      (node (ref "J11") (pin "16") (pinfunction "KL_16") (pintype "passive"))
      (node (ref "LCD1") (pin "14") (pinfunction "DB7_14") (pintype "bidirectional"))
      (node (ref "U1") (pin "29") (pinfunction "(TOSC2)PC7_29") (pintype "bidirectional"))
      (node (ref "U3") (pin "2") (pinfunction "B_2") (pintype "tri_state"))
    )
    (net (code "118") (name "PD0") (class "Default")
      (node (ref "U1") (pin "14") (pinfunction "(RXD)PD0_14") (pintype "bidirectional"))
      (node (ref "U9") (pin "12") (pinfunction "R1OUT_12") (pintype "output"))
    )
    (net (code "119") (name "PD1") (class "Default")
      (node (ref "U1") (pin "15") (pinfunction "(TXD)PD1_15") (pintype "bidirectional"))
      (node (ref "U9") (pin "11") (pinfunction "T1IN_11") (pintype "input"))
    )
    (net (code "120") (name "PD2") (class "Default")
      (node (ref "U1") (pin "16") (pinfunction "(INT0)PD2_16") (pintype "bidirectional"))
      (node (ref "U2") (pin "14") (pinfunction "OUT_14") (pintype "output"))
    )
    (net (code "121") (name "PD3") (class "Default")
      (node (ref "U1") (pin "17") (pinfunction "(INT1)PD3_17") (pintype "bidirectional"))
      (node (ref "U2") (pin "8") (pinfunction "OUT_8") (pintype "output"))
    )
    (net (code "122") (name "PD5") (class "Default")
      (node (ref "J10") (pin "15") (pinfunction "KL_15") (pintype "passive"))
      (node (ref "J11") (pin "15") (pinfunction "KL_15") (pintype "passive"))
      (node (ref "LED2") (pin "K") (pinfunction "C_K") (pintype "passive"))
      (node (ref "U1") (pin "19") (pinfunction "(OC1A)PD5_19") (pintype "bidirectional"))
    )
    (net (code "123") (name "PD6") (class "Default")
      (node (ref "J10") (pin "13") (pinfunction "KL_13") (pintype "passive"))
      (node (ref "J11") (pin "13") (pinfunction "KL_13") (pintype "passive"))
      (node (ref "LED1") (pin "K") (pinfunction "C_K") (pintype "passive"))
      (node (ref "U1") (pin "20") (pinfunction "(ICP)PD6_20") (pintype "bidirectional"))
    )
    (net (code "124") (name "PD7") (class "Default")
      (node (ref "J10") (pin "18") (pinfunction "KL_18") (pintype "passive"))
      (node (ref "J11") (pin "18") (pinfunction "KL_18") (pintype "passive"))
      (node (ref "R56") (pin "2") (pinfunction "2_2") (pintype "passive"))
      (node (ref "U1") (pin "21") (pinfunction "(OC2)PD7_21") (pintype "bidirectional"))
    )
    (net (code "125") (name "RB4") (class "Default")
      (node (ref "C27") (pin "1") (pinfunction "1_1") (pintype "passive"))
      (node (ref "C28") (pin "1") (pinfunction "1_1") (pintype "passive"))
      (node (ref "J11") (pin "7") (pinfunction "KL_7") (pintype "passive"))
    )
    (net (code "126") (name "RB9") (class "Default")
      (node (ref "C22") (pin "1") (pinfunction "1_1") (pintype "passive"))
      (node (ref "C24") (pin "2") (pinfunction "2_2") (pintype "passive"))
      (node (ref "J11") (pin "3") (pinfunction "KL_3") (pintype "passive"))
      (node (ref "R17") (pin "1") (pinfunction "1_1") (pintype "passive"))
    )
    (net (code "127") (name "RB10") (class "Default")
      (node (ref "C23") (pin "2") (pinfunction "2_2") (pintype "passive"))
      (node (ref "J11") (pin "1") (pinfunction "KL_1") (pintype "passive"))
      (node (ref "R16") (pin "1") (pinfunction "1_1") (pintype "passive"))
    )
    (net (code "128") (name "RESET") (class "Default")
      (node (ref "JP1") (pin "5") (pinfunction "S_5") (pintype "passive"))
      (node (ref "U1") (pin "9") (pinfunction "RESET_9") (pintype "input"))
    )
    (net (code "129") (name "STATE") (class "Default")
      (node (ref "J11") (pin "17") (pinfunction "KL_17") (pintype "passive"))
      (node (ref "J9") (pin "1") (pinfunction "1_1") (pintype "passive"))
    )
    (net (code "130") (name "V+") (class "Default")
      (node (ref "C1") (pin "1") (pinfunction "1_1") (pintype "passive"))
      (node (ref "C2") (pin "1") (pinfunction "1_1") (pintype "passive"))
      (node (ref "J8") (pin "PWR") (pinfunction "PWR_PWR") (pintype "bidirectional"))
      (node (ref "R3") (pin "2") (pinfunction "2_2") (pintype "passive"))
      (node (ref "U5") (pin "4") (pinfunction "IN_4") (pintype "passive"))
    )
    (net (code "131") (name "unconnected-(J2-Pad3)") (class "Default")
      (node (ref "J2") (pin "3") (pinfunction "3_3") (pintype "passive"))
    )
    (net (code "132") (name "unconnected-(J2-Pad4)") (class "Default")
      (node (ref "J2") (pin "4") (pinfunction "4_4") (pintype "passive"))
    )
    (net (code "133") (name "unconnected-(J4-Pad3)") (class "Default")
      (node (ref "J4") (pin "3") (pinfunction "3_3") (pintype "passive"))
    )
    (net (code "134") (name "unconnected-(J4-Pad4)") (class "Default")
      (node (ref "J4") (pin "4") (pinfunction "4_4") (pintype "passive"))
    )
    (net (code "135") (name "unconnected-(J6-Pad3)") (class "Default")
      (node (ref "J6") (pin "3") (pinfunction "3_3") (pintype "passive"))
    )
    (net (code "136") (name "unconnected-(J6-Pad4)") (class "Default")
      (node (ref "J6") (pin "4") (pinfunction "4_4") (pintype "passive"))
    )
    (net (code "137") (name "unconnected-(J7-Pad3)") (class "Default")
      (node (ref "J7") (pin "3") (pinfunction "3_3") (pintype "passive"))
    )
    (net (code "138") (name "unconnected-(J7-Pad4)") (class "Default")
      (node (ref "J7") (pin "4") (pinfunction "4_4") (pintype "passive"))
    )
    (net (code "139") (name "unconnected-(J9-Pad6)") (class "Default")
      (node (ref "J9") (pin "6") (pinfunction "6_6") (pintype "passive"))
    )
    (net (code "140") (name "unconnected-(LCD1-DB0-Pad7)") (class "Default")
      (node (ref "LCD1") (pin "7") (pinfunction "DB0_7") (pintype "bidirectional"))
    )
    (net (code "141") (name "unconnected-(LCD1-DB1-Pad8)") (class "Default")
      (node (ref "LCD1") (pin "8") (pinfunction "DB1_8") (pintype "bidirectional"))
    )
    (net (code "142") (name "unconnected-(LCD1-DB2-Pad9)") (class "Default")
      (node (ref "LCD1") (pin "9") (pinfunction "DB2_9") (pintype "bidirectional"))
    )
    (net (code "143") (name "unconnected-(LCD1-DB3-Pad10)") (class "Default")
      (node (ref "LCD1") (pin "10") (pinfunction "DB3_10") (pintype "bidirectional"))
    )
    (net (code "144") (name "unconnected-(U1-(SS)PB4-Pad5)") (class "Default")
      (node (ref "U1") (pin "5") (pinfunction "(SS)PB4_5") (pintype "bidirectional"))
    )
    (net (code "145") (name "unconnected-(U4B-OUT-Pad7)") (class "Default")
      (node (ref "U4") (pin "7") (pinfunction "OUT_7") (pintype "output"))
    )
    (net (code "146") (name "~{CS}") (class "Default")
      (node (ref "U1") (pin "18") (pinfunction "(OC1B)PD4_18") (pintype "bidirectional"))
      (node (ref "U8A") (pin "3") (pinfunction "~{CS}_3") (pintype "bidirectional"))
      (node (ref "U8B") (pin "1") (pinfunction "1_1") (pintype "passive"))
    )
  )
)
